# multikarya_mbed_rev_b_print.net
KiCad netlist of a schematic drawn in EAGLE
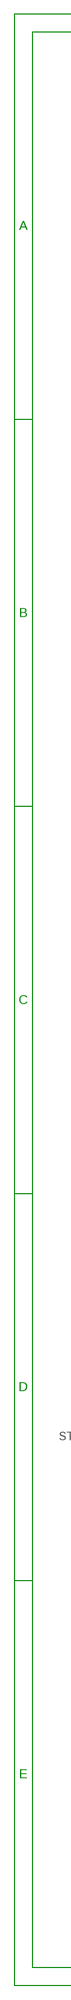
[diagram p0: schematic, sheet 1, part 1 of 2]
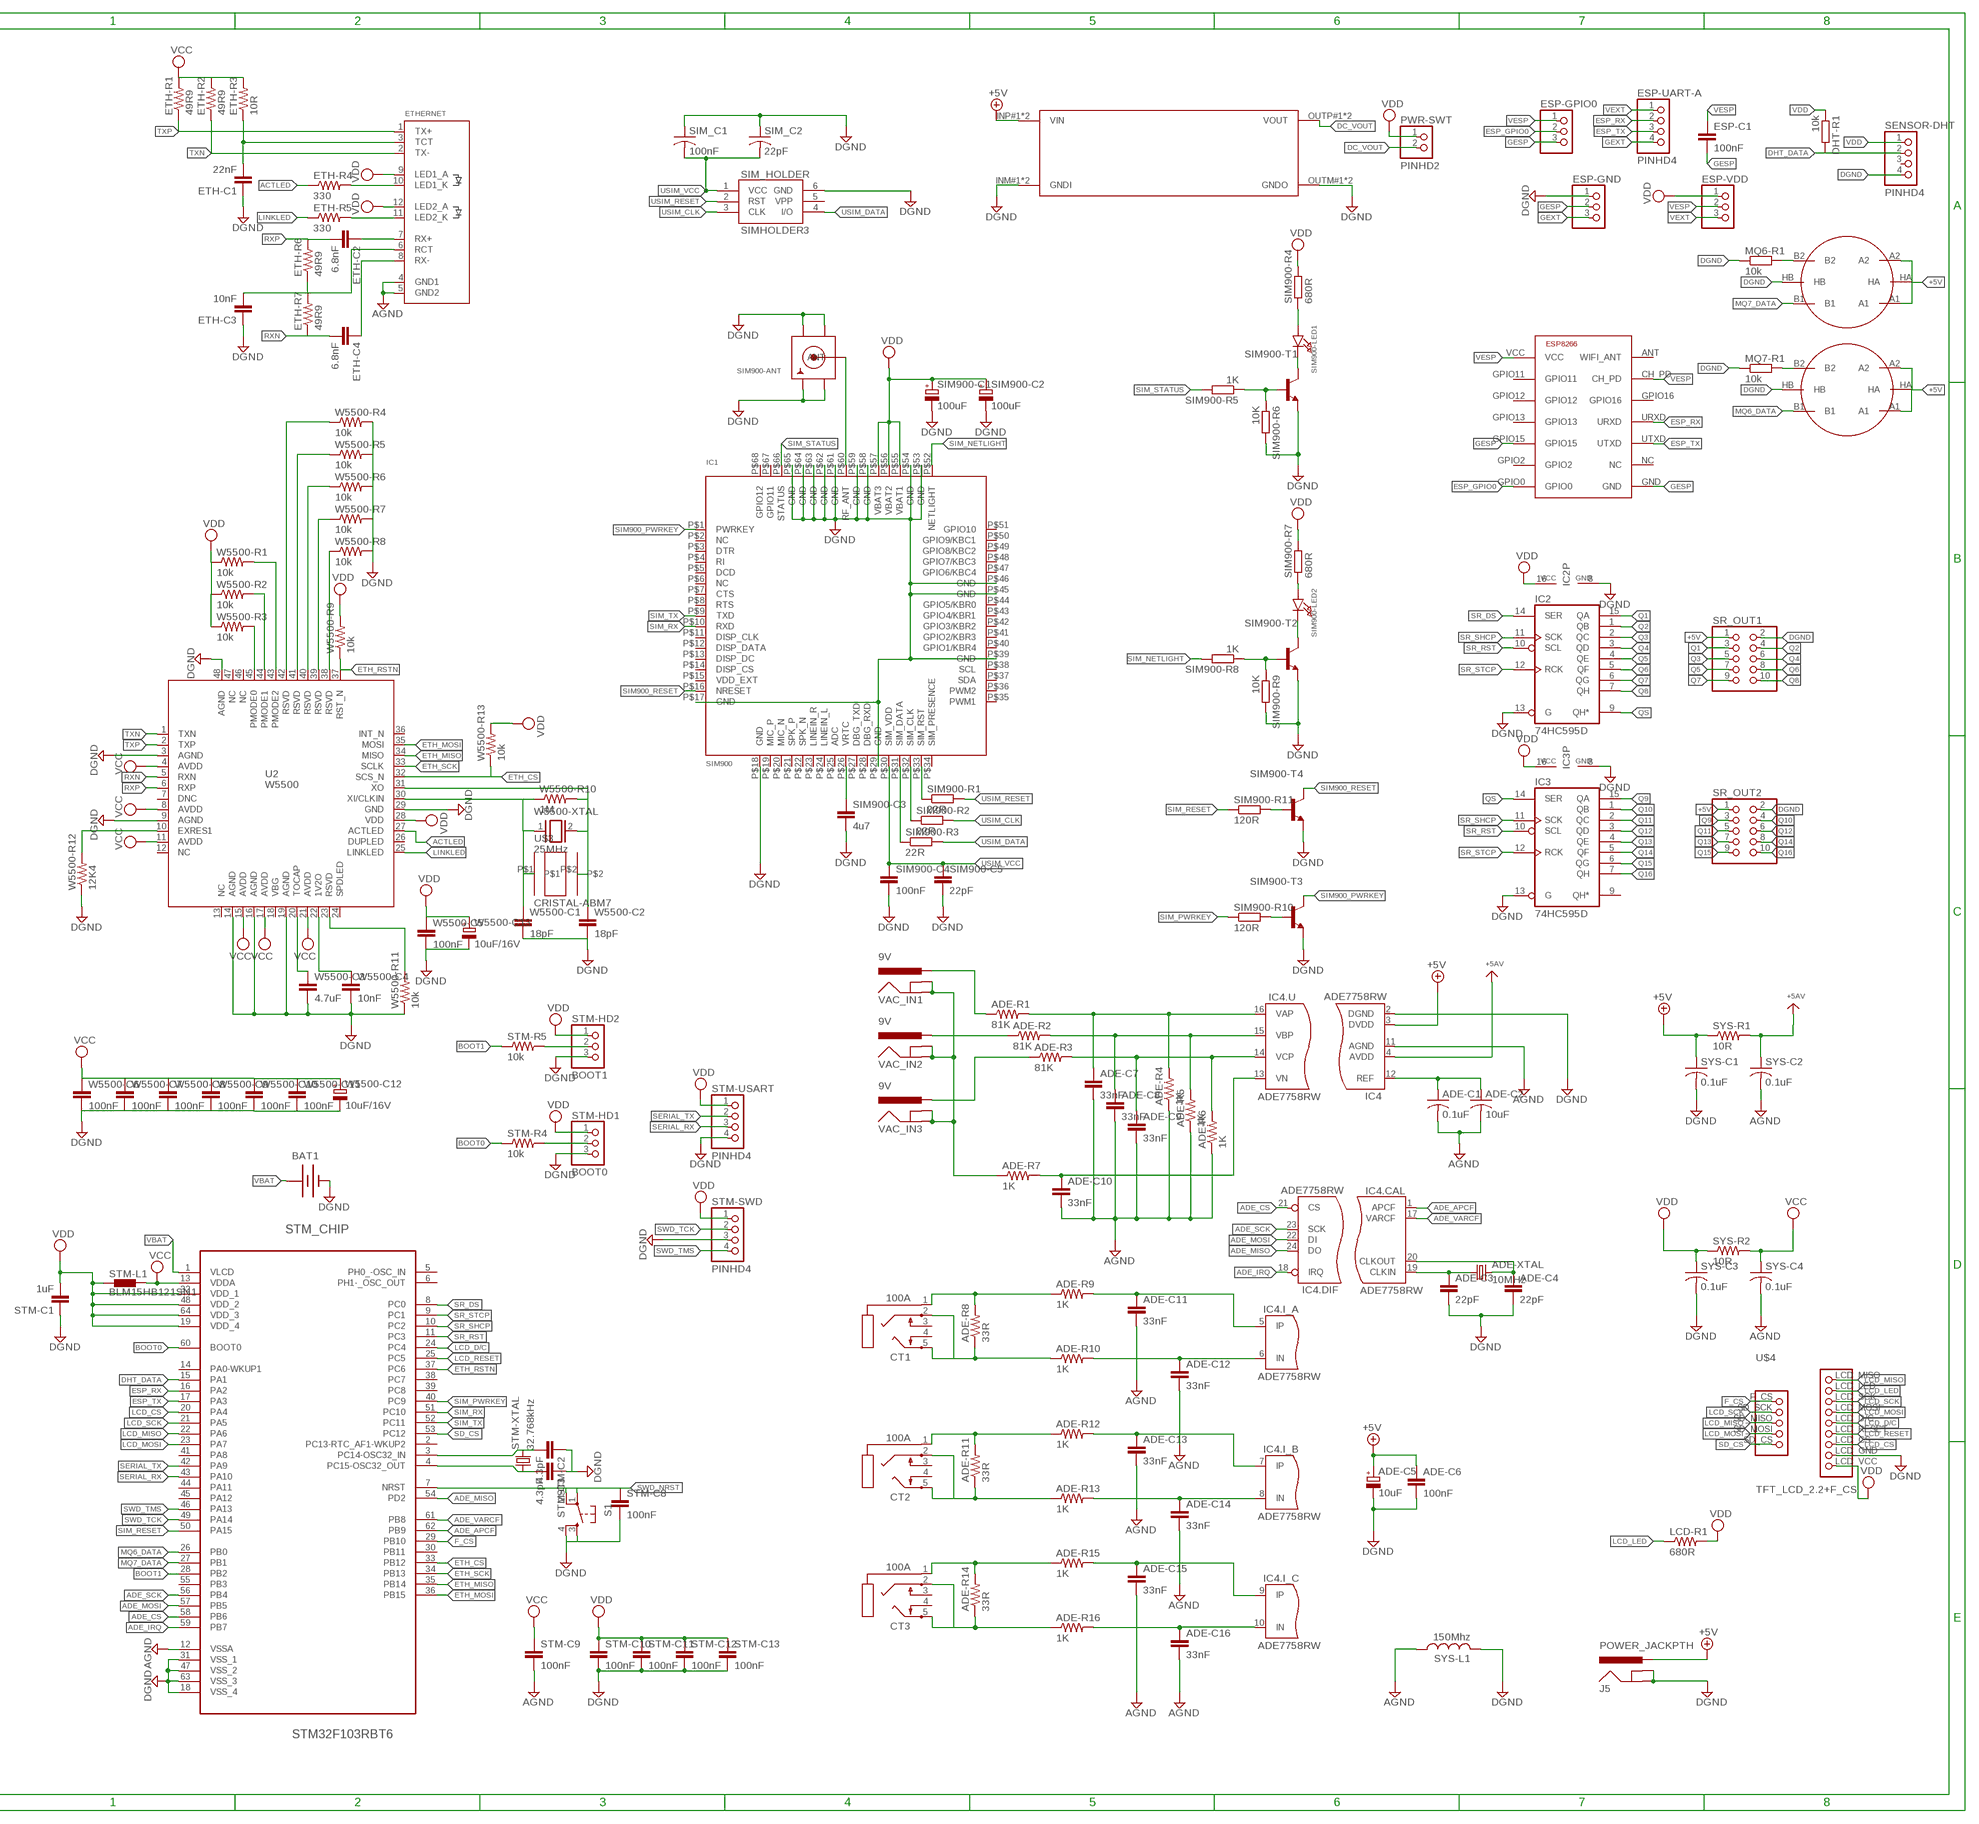
[diagram p1: schematic, sheet 1, part 2 of 2]

(export (version "E")
  (design (tool "Eeschema 10.0.6"))
  (components
    (comp (ref "ADE-C1")
      (value "0.1uF")
      (footprint "eagle-import:C0603@1")
      (libsource (lib "eagle-import") (part "C-USC0603"))
    )
    (comp (ref "ADE-C2")
      (value "10uF")
      (footprint "eagle-import:C0805K")
      (libsource (lib "eagle-import") (part "C-USC0805K"))
    )
    (comp (ref "ADE-C3")
      (value "22pF")
      (footprint "eagle-import:C0603")
      (libsource (lib "eagle-import") (part "C-EUC0603"))
    )
    (comp (ref "ADE-C4")
      (value "22pF")
      (footprint "eagle-import:C0603")
      (libsource (lib "eagle-import") (part "C-EUC0603"))
    )
    (comp (ref "ADE-C5")
      (value "10uF")
      (footprint "eagle-import:153CLV-0605")
      (libsource (lib "eagle-import") (part "CPOL-EU153CLV-0605"))
    )
    (comp (ref "ADE-C6")
      (value "100nF")
      (footprint "eagle-import:C0603")
      (libsource (lib "eagle-import") (part "C-EUC0603"))
    )
    (comp (ref "ADE-C7")
      (value "33nF")
      (footprint "eagle-import:0603-CAP")
      (libsource (lib "eagle-import") (part "CAP0603-CAP"))
    )
    (comp (ref "ADE-C8")
      (value "33nF")
      (footprint "eagle-import:0603-CAP")
      (libsource (lib "eagle-import") (part "CAP0603-CAP"))
    )
    (comp (ref "ADE-C9")
      (value "33nF")
      (footprint "eagle-import:0603-CAP")
      (libsource (lib "eagle-import") (part "CAP0603-CAP"))
    )
    (comp (ref "ADE-C10")
      (value "33nF")
      (footprint "eagle-import:0603-CAP")
      (libsource (lib "eagle-import") (part "CAP0603-CAP"))
    )
    (comp (ref "ADE-C11")
      (value "33nF")
      (footprint "eagle-import:0603-CAP")
      (libsource (lib "eagle-import") (part "CAP0603-CAP"))
    )
    (comp (ref "ADE-C12")
      (value "33nF")
      (footprint "eagle-import:0603-CAP")
      (libsource (lib "eagle-import") (part "CAP0603-CAP"))
    )
    (comp (ref "ADE-C13")
      (value "33nF")
      (footprint "eagle-import:0603-CAP")
      (libsource (lib "eagle-import") (part "CAP0603-CAP"))
    )
    (comp (ref "ADE-C14")
      (value "33nF")
      (footprint "eagle-import:0603-CAP")
      (libsource (lib "eagle-import") (part "CAP0603-CAP"))
    )
    (comp (ref "ADE-C15")
      (value "33nF")
      (footprint "eagle-import:0603-CAP")
      (libsource (lib "eagle-import") (part "CAP0603-CAP"))
    )
    (comp (ref "ADE-C16")
      (value "33nF")
      (footprint "eagle-import:0603-CAP")
      (libsource (lib "eagle-import") (part "CAP0603-CAP"))
    )
    (comp (ref "ADE-R1")
      (value "81K")
      (footprint "eagle-import:0603-RES")
      (libsource (lib "eagle-import") (part "RESISTOR0603-RES"))
    )
    (comp (ref "ADE-R2")
      (value "81K")
      (footprint "eagle-import:0603-RES")
      (libsource (lib "eagle-import") (part "RESISTOR0603-RES"))
    )
    (comp (ref "ADE-R3")
      (value "81K")
      (footprint "eagle-import:0603-RES")
      (libsource (lib "eagle-import") (part "RESISTOR0603-RES"))
    )
    (comp (ref "ADE-R4")
      (value "1K")
      (footprint "eagle-import:0603-RES")
      (libsource (lib "eagle-import") (part "RESISTOR0603-RES"))
    )
    (comp (ref "ADE-R5")
      (value "1K")
      (footprint "eagle-import:0603-RES")
      (libsource (lib "eagle-import") (part "RESISTOR0603-RES"))
    )
    (comp (ref "ADE-R6")
      (value "1K")
      (footprint "eagle-import:0603-RES")
      (libsource (lib "eagle-import") (part "RESISTOR0603-RES"))
    )
    (comp (ref "ADE-R7")
      (value "1K")
      (footprint "eagle-import:0603-RES")
      (libsource (lib "eagle-import") (part "RESISTOR0603-RES"))
    )
    (comp (ref "ADE-R8")
      (value "33R")
      (footprint "eagle-import:0603-RES")
      (libsource (lib "eagle-import") (part "RESISTOR0603-RES"))
    )
    (comp (ref "ADE-R9")
      (value "1K")
      (footprint "eagle-import:0603-RES")
      (libsource (lib "eagle-import") (part "RESISTOR0603-RES"))
    )
    (comp (ref "ADE-R10")
      (value "1K")
      (footprint "eagle-import:0603-RES")
      (libsource (lib "eagle-import") (part "RESISTOR0603-RES"))
    )
    (comp (ref "ADE-R11")
      (value "33R")
      (footprint "eagle-import:0603-RES")
      (libsource (lib "eagle-import") (part "RESISTOR0603-RES"))
    )
    (comp (ref "ADE-R12")
      (value "1K")
      (footprint "eagle-import:0603-RES")
      (libsource (lib "eagle-import") (part "RESISTOR0603-RES"))
    )
    (comp (ref "ADE-R13")
      (value "1K")
      (footprint "eagle-import:0603-RES")
      (libsource (lib "eagle-import") (part "RESISTOR0603-RES"))
    )
    (comp (ref "ADE-R14")
      (value "33R")
      (footprint "eagle-import:0603-RES")
      (libsource (lib "eagle-import") (part "RESISTOR0603-RES"))
    )
    (comp (ref "ADE-R15")
      (value "1K")
      (footprint "eagle-import:0603-RES")
      (libsource (lib "eagle-import") (part "RESISTOR0603-RES"))
    )
    (comp (ref "ADE-R16")
      (value "1K")
      (footprint "eagle-import:0603-RES")
      (libsource (lib "eagle-import") (part "RESISTOR0603-RES"))
    )
    (comp (ref "ADE-XTAL")
      (value "10MHz")
      (footprint "eagle-import:HC49US")
      (libsource (lib "eagle-import") (part "CRYSTALHC49US"))
    )
    (comp (ref "BAT1")
      (value "BATTERY20PTH")
      (footprint "eagle-import:BATTCOM_20MM_PTH")
      (libsource (lib "eagle-import") (part "BATTERY20PTH"))
    )
    (comp (ref "CT1")
      (value "100A")
      (footprint "eagle-import:STX3100")
      (libsource (lib "eagle-import") (part "AUDIO_STEREOJACK"))
    )
    (comp (ref "CT2")
      (value "100A")
      (footprint "eagle-import:STX3100")
      (libsource (lib "eagle-import") (part "AUDIO_STEREOJACK"))
    )
    (comp (ref "CT3")
      (value "100A")
      (footprint "eagle-import:STX3100")
      (libsource (lib "eagle-import") (part "AUDIO_STEREOJACK"))
    )
    (comp (ref "DCDC-3.5V")
      (value "DCDCMODULE_SMALL")
      (footprint "eagle-import:DCDCMODULE-SMALL")
      (libsource (lib "eagle-import") (part "DCDCMODULE_SMALL"))
    )
    (comp (ref "DHT-R1")
      (value "10k")
      (footprint "eagle-import:R0603")
      (libsource (lib "eagle-import") (part "resistor_R-EU_R0603"))
    )
    (comp (ref "ESP-C1")
      (value "100nF")
      (footprint "eagle-import:C0603")
      (libsource (lib "eagle-import") (part "C-EUC0603"))
    )
    (comp (ref "ESP-GND")
      (value "PINHD-1X3")
      (footprint "eagle-import:1X03")
      (libsource (lib "eagle-import") (part "PINHD-1X3"))
    )
    (comp (ref "ESP-GPIO0")
      (value "PINHD-1X3")
      (footprint "eagle-import:1X03")
      (libsource (lib "eagle-import") (part "PINHD-1X3"))
    )
    (comp (ref "ESP-UART-A")
      (value "PINHD4")
      (footprint "eagle-import:PINHD4")
      (libsource (lib "eagle-import") (part "PINHD4"))
    )
    (comp (ref "ESP-VDD")
      (value "PINHD-1X3")
      (footprint "eagle-import:1X03")
      (libsource (lib "eagle-import") (part "PINHD-1X3"))
    )
    (comp (ref "ESP8266")
      (value "ESP-07")
      (footprint "eagle-import:ESP-07")
      (libsource (lib "eagle-import") (part "ESP-07"))
    )
    (comp (ref "ETH-C1")
      (value "22nF")
      (footprint "eagle-import:C0603")
      (libsource (lib "eagle-import") (part "C-EUC0603"))
    )
    (comp (ref "ETH-C2")
      (value "6.8nF")
      (footprint "eagle-import:C0603")
      (libsource (lib "eagle-import") (part "C-EUC0603"))
    )
    (comp (ref "ETH-C3")
      (value "10nF")
      (footprint "eagle-import:C0603")
      (libsource (lib "eagle-import") (part "C-EUC0603"))
    )
    (comp (ref "ETH-C4")
      (value "6.8nF")
      (footprint "eagle-import:C0603")
      (libsource (lib "eagle-import") (part "C-EUC0603"))
    )
    (comp (ref "ETH-R1")
      (value "49R9")
      (footprint "eagle-import:R0603")
      (libsource (lib "eagle-import") (part "R-US_R0603"))
    )
    (comp (ref "ETH-R2")
      (value "49R9")
      (footprint "eagle-import:R0603")
      (libsource (lib "eagle-import") (part "R-US_R0603"))
    )
    (comp (ref "ETH-R3")
      (value "10R")
      (footprint "eagle-import:R0603")
      (libsource (lib "eagle-import") (part "R-US_R0603"))
    )
    (comp (ref "ETH-R4")
      (value "330")
      (footprint "eagle-import:R0603")
      (libsource (lib "eagle-import") (part "R-US_R0603"))
    )
    (comp (ref "ETH-R5")
      (value "330")
      (footprint "eagle-import:R0603")
      (libsource (lib "eagle-import") (part "R-US_R0603"))
    )
    (comp (ref "ETH-R6")
      (value "49R9")
      (footprint "eagle-import:R0603")
      (libsource (lib "eagle-import") (part "R-US_R0603"))
    )
    (comp (ref "ETH-R7")
      (value "49R9")
      (footprint "eagle-import:R0603")
      (libsource (lib "eagle-import") (part "R-US_R0603"))
    )
    (comp (ref "ETHERNET")
      (value "RJ45J0026D21BNL")
      (footprint "eagle-import:RJ45_PULSEJACK")
      (libsource (lib "eagle-import") (part "RJ45J0026D21BNL"))
    )
    (comp (ref "IC1")
      (value "SIM900")
      (footprint "eagle-import:SIM900_SMT")
      (libsource (lib "eagle-import") (part "GSM_SIM900_LITERAL"))
    )
    (comp (ref "IC2")
      (value "74HC595D")
      (footprint "eagle-import:SO16")
      (libsource (lib "eagle-import") (part "74595DHC"))
    )
    (comp (ref "IC3")
      (value "74HC595D")
      (footprint "eagle-import:SO16")
      (libsource (lib "eagle-import") (part "74595DHC"))
    )
    (comp (ref "IC4")
      (value "ADE7758RW")
      (footprint "eagle-import:SOIC24")
      (libsource (lib "eagle-import") (part "ADE7758RW"))
    )
    (comp (ref "J5")
      (value "POWER_JACKPTH")
      (footprint "eagle-import:POWER_JACK_PTH")
      (libsource (lib "eagle-import") (part "POWER_JACKPTH"))
    )
    (comp (ref "LCD-R1")
      (value "680R")
      (footprint "eagle-import:0603-RES")
      (libsource (lib "eagle-import") (part "RESISTOR0603-RES"))
    )
    (comp (ref "MQ6-R1")
      (value "10k")
      (footprint "eagle-import:R0603")
      (libsource (lib "eagle-import") (part "resistor_R-EU_R0603"))
    )
    (comp (ref "MQ7-R1")
      (value "10k")
      (footprint "eagle-import:R0603")
      (libsource (lib "eagle-import") (part "resistor_R-EU_R0603"))
    )
    (comp (ref "PWR-SWT")
      (value "PINHD2")
      (footprint "eagle-import:PINHD2")
      (libsource (lib "eagle-import") (part "PINHD2"))
    )
    (comp (ref "S1")
      (value "TAC_SWITCHPTH")
      (footprint "eagle-import:TACTILE-PTH")
      (libsource (lib "eagle-import") (part "TAC_SWITCHPTH"))
    )
    (comp (ref "SENSOR-DHT")
      (value "PINHD4")
      (footprint "eagle-import:PINHD4")
      (libsource (lib "eagle-import") (part "PINHD4"))
    )
    (comp (ref "SENSOR-MQ6")
      (value "METHANE_SENSOR")
      (footprint "eagle-import:MQ-3")
      (libsource (lib "eagle-import") (part "METHANE_SENSOR"))
    )
    (comp (ref "SENSOR-MQ7")
      (value "METHANE_SENSOR")
      (footprint "eagle-import:MQ-3")
      (libsource (lib "eagle-import") (part "METHANE_SENSOR"))
    )
    (comp (ref "SIM900-ANT")
      (value "SMACONNECTOR")
      (footprint "eagle-import:SMA90_DIP")
      (libsource (lib "eagle-import") (part "SMACONNECTOR"))
    )
    (comp (ref "SIM900-C1")
      (value "100uF")
      (footprint "eagle-import:153CLV-0605")
      (libsource (lib "eagle-import") (part "CPOL-EU153CLV-0605"))
    )
    (comp (ref "SIM900-C2")
      (value "100uF")
      (footprint "eagle-import:153CLV-0605")
      (libsource (lib "eagle-import") (part "CPOL-EU153CLV-0605"))
    )
    (comp (ref "SIM900-C3")
      (value "4u7")
      (footprint "eagle-import:C0603")
      (libsource (lib "eagle-import") (part "C-EUC0603"))
    )
    (comp (ref "SIM900-C4")
      (value "100nF")
      (footprint "eagle-import:C0603")
      (libsource (lib "eagle-import") (part "C-EUC0603"))
    )
    (comp (ref "SIM900-C5")
      (value "22pF")
      (footprint "eagle-import:C0603")
      (libsource (lib "eagle-import") (part "C-EUC0603"))
    )
    (comp (ref "SIM900-LED1")
      (value "LED0805_NOOUTLINE")
      (footprint "eagle-import:CHIPLED_0805_NOOUTLINE")
      (libsource (lib "eagle-import") (part "LED0805_NOOUTLINE"))
    )
    (comp (ref "SIM900-LED2")
      (value "LED0805_NOOUTLINE")
      (footprint "eagle-import:CHIPLED_0805_NOOUTLINE")
      (libsource (lib "eagle-import") (part "LED0805_NOOUTLINE"))
    )
    (comp (ref "SIM900-R1")
      (value "22R")
      (footprint "eagle-import:R0603")
      (libsource (lib "eagle-import") (part "R-EU_R0603"))
    )
    (comp (ref "SIM900-R2")
      (value "22R")
      (footprint "eagle-import:R0603")
      (libsource (lib "eagle-import") (part "R-EU_R0603"))
    )
    (comp (ref "SIM900-R3")
      (value "22R")
      (footprint "eagle-import:R0603")
      (libsource (lib "eagle-import") (part "R-EU_R0603"))
    )
    (comp (ref "SIM900-R4")
      (value "680R")
      (footprint "eagle-import:R0603")
      (libsource (lib "eagle-import") (part "R-EU_R0603"))
    )
    (comp (ref "SIM900-R5")
      (value "1K")
      (footprint "eagle-import:R0603")
      (libsource (lib "eagle-import") (part "R-EU_R0603"))
    )
    (comp (ref "SIM900-R6")
      (value "10K")
      (footprint "eagle-import:R0603")
      (libsource (lib "eagle-import") (part "R-EU_R0603"))
    )
    (comp (ref "SIM900-R7")
      (value "680R")
      (footprint "eagle-import:R0603")
      (libsource (lib "eagle-import") (part "R-EU_R0603"))
    )
    (comp (ref "SIM900-R8")
      (value "1K")
      (footprint "eagle-import:R0603")
      (libsource (lib "eagle-import") (part "R-EU_R0603"))
    )
    (comp (ref "SIM900-R9")
      (value "10K")
      (footprint "eagle-import:R0603")
      (libsource (lib "eagle-import") (part "R-EU_R0603"))
    )
    (comp (ref "SIM900-R10")
      (value "120R")
      (footprint "eagle-import:R0603")
      (libsource (lib "eagle-import") (part "resistor_R-EU_R0603"))
    )
    (comp (ref "SIM900-R11")
      (value "120R")
      (footprint "eagle-import:R0603")
      (libsource (lib "eagle-import") (part "resistor_R-EU_R0603"))
    )
    (comp (ref "SIM900-T1")
      (value "MMBT2222ALT1-NPN-SOT23-BEC")
      (footprint "eagle-import:SOT23-BEC")
      (libsource (lib "eagle-import") (part "-NPN-SOT23-BECMMBT2222ALT1"))
    )
    (comp (ref "SIM900-T2")
      (value "MMBT2222ALT1-NPN-SOT23-BEC")
      (footprint "eagle-import:SOT23-BEC")
      (libsource (lib "eagle-import") (part "-NPN-SOT23-BECMMBT2222ALT1"))
    )
    (comp (ref "SIM900-T3")
      (value "MMBT2222ALT1-NPN-SOT23-BEC")
      (footprint "eagle-import:SOT23-BEC")
      (libsource (lib "eagle-import") (part "transistor-neu-to92_-NPN-SOT23-BECMMBT2222ALT1"))
    )
    (comp (ref "SIM900-T4")
      (value "MMBT2222ALT1-NPN-SOT23-BEC")
      (footprint "eagle-import:SOT23-BEC")
      (libsource (lib "eagle-import") (part "transistor-neu-to92_-NPN-SOT23-BECMMBT2222ALT1"))
    )
    (comp (ref "SIM_C1")
      (value "100nF")
      (footprint "eagle-import:C0603K")
      (libsource (lib "eagle-import") (part "C-USC0603K"))
    )
    (comp (ref "SIM_C2")
      (value "22pF")
      (footprint "eagle-import:C0603K")
      (libsource (lib "eagle-import") (part "C-USC0603K"))
    )
    (comp (ref "SIM_HOLDER")
      (value "SIMHOLDER3")
      (footprint "eagle-import:SIMHOLDER3")
      (libsource (lib "eagle-import") (part "SIMHOLDER3"))
    )
    (comp (ref "SR_OUT1")
      (value "PINHD-2X5/90")
      (footprint "eagle-import:2X05_90")
      (libsource (lib "eagle-import") (part "PINHD-2X5/90"))
    )
    (comp (ref "SR_OUT2")
      (value "PINHD-2X5/90")
      (footprint "eagle-import:2X05_90")
      (libsource (lib "eagle-import") (part "PINHD-2X5/90"))
    )
    (comp (ref "STM-C1")
      (value "1uF")
      (footprint "eagle-import:C0603")
      (libsource (lib "eagle-import") (part "C-EUC0603"))
    )
    (comp (ref "STM-C2")
      (value "4.3pF")
      (footprint "eagle-import:C0603")
      (libsource (lib "eagle-import") (part "C-EUC0603"))
    )
    (comp (ref "STM-C3")
      (value "4.3pF")
      (footprint "eagle-import:C0603")
      (libsource (lib "eagle-import") (part "C-EUC0603"))
    )
    (comp (ref "STM-C8")
      (value "100nF")
      (footprint "eagle-import:C0603")
      (libsource (lib "eagle-import") (part "C-EUC0603"))
    )
    (comp (ref "STM-C9")
      (value "100nF")
      (footprint "eagle-import:C0603")
      (libsource (lib "eagle-import") (part "C-EUC0603"))
    )
    (comp (ref "STM-C10")
      (value "100nF")
      (footprint "eagle-import:C0603")
      (libsource (lib "eagle-import") (part "C-EUC0603"))
    )
    (comp (ref "STM-C11")
      (value "100nF")
      (footprint "eagle-import:C0603")
      (libsource (lib "eagle-import") (part "C-EUC0603"))
    )
    (comp (ref "STM-C12")
      (value "100nF")
      (footprint "eagle-import:C0603")
      (libsource (lib "eagle-import") (part "C-EUC0603"))
    )
    (comp (ref "STM-C13")
      (value "100nF")
      (footprint "eagle-import:C0603")
      (libsource (lib "eagle-import") (part "C-EUC0603"))
    )
    (comp (ref "STM-HD1")
      (value "BOOT0")
      (footprint "eagle-import:1X03")
      (libsource (lib "eagle-import") (part "PINHD-1X3"))
    )
    (comp (ref "STM-HD2")
      (value "BOOT1")
      (footprint "eagle-import:1X03")
      (libsource (lib "eagle-import") (part "PINHD-1X3"))
    )
    (comp (ref "STM-L1")
      (value "BLM15HB121SN1")
      (footprint "eagle-import:0402")
      (libsource (lib "eagle-import") (part "BLM15HB121SN1"))
    )
    (comp (ref "STM-R4")
      (value "10k")
      (footprint "eagle-import:R0603")
      (libsource (lib "eagle-import") (part "R-US_R0603"))
    )
    (comp (ref "STM-R5")
      (value "10k")
      (footprint "eagle-import:R0603")
      (libsource (lib "eagle-import") (part "R-US_R0603"))
    )
    (comp (ref "STM-SWD")
      (value "PINHD4")
      (footprint "eagle-import:PINHD4")
      (libsource (lib "eagle-import") (part "PINHD4"))
    )
    (comp (ref "STM-USART")
      (value "PINHD4")
      (footprint "eagle-import:PINHD4")
      (libsource (lib "eagle-import") (part "PINHD4"))
    )
    (comp (ref "STM-XTAL")
      (value "32.768kHz")
      (footprint "eagle-import:TC26H")
      (libsource (lib "eagle-import") (part "CRYSTALTC26H"))
    )
    (comp (ref "STM_CHIP")
      (value "STM32F103RBT6")
      (footprint "eagle-import:QFP50P1200X1200X160-64N")
      (fields (field (name "MPN") "STM32L152RBT6"))
      (libsource (lib "eagle-import") (part "STM32L152RBT6"))
    )
    (comp (ref "SYS-C1")
      (value "0.1uF")
      (footprint "eagle-import:C0603@1")
      (libsource (lib "eagle-import") (part "C-USC0603"))
    )
    (comp (ref "SYS-C2")
      (value "0.1uF")
      (footprint "eagle-import:C0603@1")
      (libsource (lib "eagle-import") (part "C-USC0603"))
    )
    (comp (ref "SYS-C3")
      (value "0.1uF")
      (footprint "eagle-import:C0603@1")
      (libsource (lib "eagle-import") (part "C-USC0603"))
    )
    (comp (ref "SYS-C4")
      (value "0.1uF")
      (footprint "eagle-import:C0603@1")
      (libsource (lib "eagle-import") (part "C-USC0603"))
    )
    (comp (ref "SYS-L1")
      (value "150Mhz")
      (footprint "eagle-import:POWER-CHOKE_WE-TPC")
      (libsource (lib "eagle-import") (part "L-USWE-TPC"))
    )
    (comp (ref "SYS-R1")
      (value "10R")
      (footprint "eagle-import:0603-RES")
      (libsource (lib "eagle-import") (part "RESISTOR0603-RES"))
    )
    (comp (ref "SYS-R2")
      (value "10R")
      (footprint "eagle-import:0603-RES")
      (libsource (lib "eagle-import") (part "RESISTOR0603-RES"))
    )
    (comp (ref "U$3")
      (value "CRISTAL-ABM7")
      (footprint "eagle-import:CRISTAL-ABM7")
      (libsource (lib "eagle-import") (part "CRISTAL-ABM7"))
    )
    (comp (ref "U$4")
      (value "TFT_LCD_2.2+F_CS")
      (footprint "eagle-import:TFT_LCD_2.2+F_CS")
      (libsource (lib "eagle-import") (part "TFT_LCD_2.2+F_CS"))
    )
    (comp (ref "U2")
      (value "W5500")
      (footprint "eagle-import:W5500")
      (libsource (lib "eagle-import") (part "W5500"))
    )
    (comp (ref "VAC_IN1")
      (value "9V")
      (footprint "eagle-import:POWER_JACK_PTH")
      (libsource (lib "eagle-import") (part "POWER_JACKPTH"))
    )
    (comp (ref "VAC_IN2")
      (value "9V")
      (footprint "eagle-import:POWER_JACK_PTH")
      (libsource (lib "eagle-import") (part "POWER_JACKPTH"))
    )
    (comp (ref "VAC_IN3")
      (value "9V")
      (footprint "eagle-import:POWER_JACK_PTH")
      (libsource (lib "eagle-import") (part "POWER_JACKPTH"))
    )
    (comp (ref "W5500-C1")
      (value "18pF")
      (footprint "eagle-import:C0603")
      (libsource (lib "eagle-import") (part "C-EUC0603"))
    )
    (comp (ref "W5500-C2")
      (value "18pF")
      (footprint "eagle-import:C0603")
      (libsource (lib "eagle-import") (part "C-EUC0603"))
    )
    (comp (ref "W5500-C3")
      (value "4.7uF")
      (footprint "eagle-import:C0603")
      (libsource (lib "eagle-import") (part "C-EUC0603"))
    )
    (comp (ref "W5500-C4")
      (value "10nF")
      (footprint "eagle-import:C0603")
      (libsource (lib "eagle-import") (part "C-EUC0603"))
    )
    (comp (ref "W5500-C5")
      (value "100nF")
      (footprint "eagle-import:C0603")
      (libsource (lib "eagle-import") (part "C-EUC0603"))
    )
    (comp (ref "W5500-C6")
      (value "100nF")
      (footprint "eagle-import:C0603")
      (libsource (lib "eagle-import") (part "C-EUC0603"))
    )
    (comp (ref "W5500-C7")
      (value "100nF")
      (footprint "eagle-import:C0603")
      (libsource (lib "eagle-import") (part "C-EUC0603"))
    )
    (comp (ref "W5500-C8")
      (value "100nF")
      (footprint "eagle-import:C0603")
      (libsource (lib "eagle-import") (part "C-EUC0603"))
    )
    (comp (ref "W5500-C9")
      (value "100nF")
      (footprint "eagle-import:C0603")
      (libsource (lib "eagle-import") (part "C-EUC0603"))
    )
    (comp (ref "W5500-C10")
      (value "100nF")
      (footprint "eagle-import:C0603")
      (libsource (lib "eagle-import") (part "C-EUC0603"))
    )
    (comp (ref "W5500-C11")
      (value "100nF")
      (footprint "eagle-import:C0603")
      (libsource (lib "eagle-import") (part "C-EUC0603"))
    )
    (comp (ref "W5500-C12")
      (value "10uF/16V")
      (footprint "eagle-import:153CLV-0605")
      (libsource (lib "eagle-import") (part "CPOL-EU153CLV-0605"))
    )
    (comp (ref "W5500-C13")
      (value "10uF/16V")
      (footprint "eagle-import:153CLV-0605")
      (libsource (lib "eagle-import") (part "CPOL-EU153CLV-0605"))
    )
    (comp (ref "W5500-R1")
      (value "10k")
      (footprint "eagle-import:R0603")
      (libsource (lib "eagle-import") (part "R-US_R0603"))
    )
    (comp (ref "W5500-R2")
      (value "10k")
      (footprint "eagle-import:R0603")
      (libsource (lib "eagle-import") (part "R-US_R0603"))
    )
    (comp (ref "W5500-R3")
      (value "10k")
      (footprint "eagle-import:R0603")
      (libsource (lib "eagle-import") (part "R-US_R0603"))
    )
    (comp (ref "W5500-R4")
      (value "10k")
      (footprint "eagle-import:R0603")
      (libsource (lib "eagle-import") (part "R-US_R0603"))
    )
    (comp (ref "W5500-R5")
      (value "10k")
      (footprint "eagle-import:R0603")
      (libsource (lib "eagle-import") (part "R-US_R0603"))
    )
    (comp (ref "W5500-R6")
      (value "10k")
      (footprint "eagle-import:R0603")
      (libsource (lib "eagle-import") (part "R-US_R0603"))
    )
    (comp (ref "W5500-R7")
      (value "10k")
      (footprint "eagle-import:R0603")
      (libsource (lib "eagle-import") (part "R-US_R0603"))
    )
    (comp (ref "W5500-R8")
      (value "10k")
      (footprint "eagle-import:R0603")
      (libsource (lib "eagle-import") (part "R-US_R0603"))
    )
    (comp (ref "W5500-R9")
      (value "10k")
      (footprint "eagle-import:R0603")
      (libsource (lib "eagle-import") (part "R-US_R0603"))
    )
    (comp (ref "W5500-R10")
      (value "1M")
      (footprint "eagle-import:R0603")
      (libsource (lib "eagle-import") (part "R-US_R0603"))
    )
    (comp (ref "W5500-R11")
      (value "10k")
      (footprint "eagle-import:R0603")
      (libsource (lib "eagle-import") (part "R-US_R0603"))
    )
    (comp (ref "W5500-R12")
      (value "12K4")
      (footprint "eagle-import:R0805")
      (libsource (lib "eagle-import") (part "R-US_R0805"))
    )
    (comp (ref "W5500-R13")
      (value "10k")
      (footprint "eagle-import:R0603")
      (libsource (lib "eagle-import") (part "R-US_R0603"))
    )
    (comp (ref "W5500-XTAL")
      (value "25MHz")
      (footprint "eagle-import:QS")
      (libsource (lib "eagle-import") (part "XTAL/S"))
    )
  )
  (nets
    (net (code "1") (name "+5AV") (class "Default")
      (node (ref "IC4") (pin "4") (pinfunction "AVDD_4") (pintype "power_in"))
      (node (ref "SYS-C2") (pin "1") (pinfunction "1_1") (pintype "passive"))
      (node (ref "SYS-R1") (pin "2") (pinfunction "2_2") (pintype "passive"))
    )
    (net (code "2") (name "+5V") (class "Default")
      (node (ref "ADE-C5") (pin "+") (pinfunction "+_+") (pintype "passive"))
      (node (ref "ADE-C6") (pin "1") (pinfunction "1_1") (pintype "passive"))
      (node (ref "DCDC-3.5V") (pin "INP#1") (pinfunction "VIN_INP#1") (pintype "bidirectional"))
      (node (ref "DCDC-3.5V") (pin "INP#2") (pinfunction "VIN_INP#2") (pintype "bidirectional"))
      (node (ref "IC4") (pin "3") (pinfunction "DVDD_3") (pintype "power_in"))
      (node (ref "J5") (pin "PWR") (pinfunction "PWR_PWR") (pintype "bidirectional"))
      (node (ref "SENSOR-MQ6") (pin "A1") (pinfunction "A1_A1") (pintype "bidirectional"))
      (node (ref "SENSOR-MQ6") (pin "A2") (pinfunction "A2_A2") (pintype "bidirectional"))
      (node (ref "SENSOR-MQ6") (pin "HA") (pinfunction "HA_HA") (pintype "bidirectional"))
      (node (ref "SENSOR-MQ7") (pin "A1") (pinfunction "A1_A1") (pintype "bidirectional"))
      (node (ref "SENSOR-MQ7") (pin "A2") (pinfunction "A2_A2") (pintype "bidirectional"))
      (node (ref "SENSOR-MQ7") (pin "HA") (pinfunction "HA_HA") (pintype "bidirectional"))
      (node (ref "SR_OUT1") (pin "1") (pinfunction "1_1") (pintype "passive"))
      (node (ref "SR_OUT2") (pin "1") (pinfunction "1_1") (pintype "passive"))
      (node (ref "SYS-C1") (pin "1") (pinfunction "1_1") (pintype "passive"))
      (node (ref "SYS-R1") (pin "1") (pinfunction "1_1") (pintype "passive"))
    )
    (net (code "3") (name "/GPIO11") (class "Default")
      (node (ref "IC1") (pin "P$67") (pinfunction "GPIO11_P$67") (pintype "power_in"))
    )
    (net (code "4") (name "/GPIO12") (class "Default")
      (node (ref "IC1") (pin "P$68") (pinfunction "GPIO12_P$68") (pintype "power_in"))
    )
    (net (code "5") (name "ACTLED") (class "Default")
      (node (ref "ETH-R4") (pin "1") (pinfunction "1_1") (pintype "passive"))
      (node (ref "U2") (pin "27") (pinfunction "ACTLED_27") (pintype "passive"))
    )
    (net (code "6") (name "ADE_APCF") (class "Default")
      (node (ref "IC4") (pin "1") (pinfunction "APCF_1") (pintype "output"))
      (node (ref "STM_CHIP") (pin "62") (pinfunction "PB9_62") (pintype "bidirectional"))
    )
    (net (code "7") (name "ADE_CS") (class "Default")
      (node (ref "IC4") (pin "21") (pinfunction "CS_21") (pintype "input"))
      (node (ref "STM_CHIP") (pin "58") (pinfunction "PB6_58") (pintype "bidirectional"))
    )
    (net (code "8") (name "ADE_IRQ") (class "Default")
      (node (ref "IC4") (pin "18") (pinfunction "IRQ_18") (pintype "output"))
      (node (ref "STM_CHIP") (pin "59") (pinfunction "PB7_59") (pintype "bidirectional"))
    )
    (net (code "9") (name "ADE_MISO") (class "Default")
      (node (ref "IC4") (pin "24") (pinfunction "DO_24") (pintype "output"))
      (node (ref "STM_CHIP") (pin "54") (pinfunction "PD2_54") (pintype "bidirectional"))
    )
    (net (code "10") (name "ADE_MOSI") (class "Default")
      (node (ref "IC4") (pin "22") (pinfunction "DI_22") (pintype "input"))
      (node (ref "STM_CHIP") (pin "57") (pinfunction "PB5_57") (pintype "bidirectional"))
    )
    (net (code "11") (name "ADE_SCK") (class "Default")
      (node (ref "IC4") (pin "23") (pinfunction "SCK_23") (pintype "input"))
      (node (ref "STM_CHIP") (pin "56") (pinfunction "PB4_56") (pintype "bidirectional"))
    )
    (net (code "12") (name "ADE_VARCF") (class "Default")
      (node (ref "IC4") (pin "17") (pinfunction "VARCF_17") (pintype "output"))
      (node (ref "STM_CHIP") (pin "61") (pinfunction "PB8_61") (pintype "bidirectional"))
    )
    (net (code "13") (name "AGND") (class "Default")
      (node (ref "ADE-C1") (pin "2") (pinfunction "2_2") (pintype "passive"))
      (node (ref "ADE-C10") (pin "2") (pinfunction "2_2") (pintype "passive"))
      (node (ref "ADE-C11") (pin "2") (pinfunction "2_2") (pintype "passive"))
      (node (ref "ADE-C12") (pin "2") (pinfunction "2_2") (pintype "passive"))
      (node (ref "ADE-C13") (pin "2") (pinfunction "2_2") (pintype "passive"))
      (node (ref "ADE-C14") (pin "2") (pinfunction "2_2") (pintype "passive"))
      (node (ref "ADE-C15") (pin "2") (pinfunction "2_2") (pintype "passive"))
      (node (ref "ADE-C16") (pin "2") (pinfunction "2_2") (pintype "passive"))
      (node (ref "ADE-C2") (pin "2") (pinfunction "2_2") (pintype "passive"))
      (node (ref "ADE-C7") (pin "2") (pinfunction "2_2") (pintype "passive"))
      (node (ref "ADE-C8") (pin "2") (pinfunction "2_2") (pintype "passive"))
      (node (ref "ADE-C9") (pin "2") (pinfunction "2_2") (pintype "passive"))
      (node (ref "ADE-R4") (pin "1") (pinfunction "1_1") (pintype "passive"))
      (node (ref "ADE-R5") (pin "1") (pinfunction "1_1") (pintype "passive"))
      (node (ref "ADE-R6") (pin "1") (pinfunction "1_1") (pintype "passive"))
      (node (ref "ETHERNET") (pin "4") (pinfunction "GND1_4") (pintype "bidirectional"))
      (node (ref "ETHERNET") (pin "5") (pinfunction "GND2_5") (pintype "bidirectional"))
      (node (ref "IC4") (pin "11") (pinfunction "AGND_11") (pintype "power_in"))
      (node (ref "STM-C9") (pin "2") (pinfunction "2_2") (pintype "passive"))
      (node (ref "STM_CHIP") (pin "12") (pinfunction "VSSA_12") (pintype "power_in"))
      (node (ref "SYS-C2") (pin "2") (pinfunction "2_2") (pintype "passive"))
      (node (ref "SYS-C4") (pin "2") (pinfunction "2_2") (pintype "passive"))
      (node (ref "SYS-L1") (pin "1") (pinfunction "1_1") (pintype "passive"))
    )
    (net (code "14") (name "BOOT0") (class "Default")
      (node (ref "STM-R4") (pin "1") (pinfunction "1_1") (pintype "passive"))
      (node (ref "STM_CHIP") (pin "60") (pinfunction "BOOT0_60") (pintype "input"))
    )
    (net (code "15") (name "BOOT1") (class "Default")
      (node (ref "STM-R5") (pin "1") (pinfunction "1_1") (pintype "passive"))
      (node (ref "STM_CHIP") (pin "28") (pinfunction "PB2_28") (pintype "bidirectional"))
    )
    (net (code "16") (name "DC_VOUT") (class "Default")
      (node (ref "DCDC-3.5V") (pin "OUTP#1") (pinfunction "VOUT_OUTP#1") (pintype "bidirectional"))
      (node (ref "DCDC-3.5V") (pin "OUTP#2") (pinfunction "VOUT_OUTP#2") (pintype "bidirectional"))
      (node (ref "PWR-SWT") (pin "2") (pinfunction "2_2") (pintype "passive"))
    )
    (net (code "17") (name "DGND") (class "Default")
      (node (ref "ADE-C3") (pin "2") (pinfunction "2_2") (pintype "passive"))
      (node (ref "ADE-C4") (pin "2") (pinfunction "2_2") (pintype "passive"))
      (node (ref "ADE-C5") (pin "-") (pinfunction "-_-") (pintype "passive"))
      (node (ref "ADE-C6") (pin "2") (pinfunction "2_2") (pintype "passive"))
      (node (ref "BAT1") (pin "2") (pinfunction "-_2") (pintype "power_in"))
      (node (ref "DCDC-3.5V") (pin "INM#1") (pinfunction "GNDI_INM#1") (pintype "bidirectional"))
      (node (ref "DCDC-3.5V") (pin "INM#2") (pinfunction "GNDI_INM#2") (pintype "bidirectional"))
      (node (ref "DCDC-3.5V") (pin "OUTM#1") (pinfunction "GNDO_OUTM#1") (pintype "bidirectional"))
      (node (ref "DCDC-3.5V") (pin "OUTM#2") (pinfunction "GNDO_OUTM#2") (pintype "bidirectional"))
      (node (ref "ESP-GND") (pin "1") (pinfunction "1_1") (pintype "passive"))
      (node (ref "ETH-C1") (pin "1") (pinfunction "1_1") (pintype "passive"))
      (node (ref "ETH-C3") (pin "1") (pinfunction "1_1") (pintype "passive"))
      (node (ref "IC1") (pin "P$17") (pinfunction "GND_P$17") (pintype "power_in"))
      (node (ref "IC1") (pin "P$18") (pinfunction "GND_P$18") (pintype "power_in"))
      (node (ref "IC1") (pin "P$29") (pinfunction "GND_P$29") (pintype "power_in"))
      (node (ref "IC1") (pin "P$39") (pinfunction "GND_P$39") (pintype "power_in"))
      (node (ref "IC1") (pin "P$45") (pinfunction "GND_P$45") (pintype "power_in"))
      (node (ref "IC1") (pin "P$46") (pinfunction "GND_P$46") (pintype "power_in"))
      (node (ref "IC1") (pin "P$53") (pinfunction "GND_P$53") (pintype "power_in"))
      (node (ref "IC1") (pin "P$54") (pinfunction "GND_P$54") (pintype "power_in"))
      (node (ref "IC1") (pin "P$58") (pinfunction "GND_P$58") (pintype "power_in"))
      (node (ref "IC1") (pin "P$59") (pinfunction "GND_P$59") (pintype "power_in"))
      (node (ref "IC1") (pin "P$61") (pinfunction "GND_P$61") (pintype "power_in"))
      (node (ref "IC1") (pin "P$62") (pinfunction "GND_P$62") (pintype "power_in"))
      (node (ref "IC1") (pin "P$63") (pinfunction "GND_P$63") (pintype "power_in"))
      (node (ref "IC1") (pin "P$64") (pinfunction "GND_P$64") (pintype "power_in"))
      (node (ref "IC1") (pin "P$65") (pinfunction "GND_P$65") (pintype "power_in"))
      (node (ref "IC2") (pin "13") (pinfunction "G_13") (pintype "input"))
      (node (ref "IC2") (pin "8") (pinfunction "GND_8") (pintype "power_in"))
      (node (ref "IC3") (pin "13") (pinfunction "G_13") (pintype "input"))
      (node (ref "IC3") (pin "8") (pinfunction "GND_8") (pintype "power_in"))
      (node (ref "IC4") (pin "2") (pinfunction "DGND_2") (pintype "power_in"))
      (node (ref "J5") (pin "GND") (pinfunction "GND_GND") (pintype "bidirectional"))
      (node (ref "J5") (pin "GNDBREAK") (pinfunction "GNDBREAK_GNDBREAK") (pintype "bidirectional"))
      (node (ref "MQ6-R1") (pin "1") (pinfunction "1_1") (pintype "passive"))
      (node (ref "MQ7-R1") (pin "1") (pinfunction "1_1") (pintype "passive"))
      (node (ref "S1") (pin "3") (pinfunction "3_3") (pintype "passive"))
      (node (ref "S1") (pin "4") (pinfunction "4_4") (pintype "passive"))
      (node (ref "SENSOR-DHT") (pin "4") (pinfunction "4_4") (pintype "passive"))
      (node (ref "SENSOR-MQ6") (pin "HB") (pinfunction "HB_HB") (pintype "bidirectional"))
      (node (ref "SENSOR-MQ7") (pin "HB") (pinfunction "HB_HB") (pintype "bidirectional"))
      (node (ref "SIM900-ANT") (pin "GND1") (pinfunction "GND1_GND1") (pintype "power_in"))
      (node (ref "SIM900-ANT") (pin "GND2") (pinfunction "GND2_GND2") (pintype "power_in"))
      (node (ref "SIM900-ANT") (pin "GND3") (pinfunction "GND3_GND3") (pintype "power_in"))
      (node (ref "SIM900-ANT") (pin "GND4") (pinfunction "GND4_GND4") (pintype "power_in"))
      (node (ref "SIM900-C1") (pin "-") (pinfunction "-_-") (pintype "passive"))
      (node (ref "SIM900-C2") (pin "-") (pinfunction "-_-") (pintype "passive"))
      (node (ref "SIM900-C3") (pin "2") (pinfunction "2_2") (pintype "passive"))
      (node (ref "SIM900-C4") (pin "2") (pinfunction "2_2") (pintype "passive"))
      (node (ref "SIM900-C5") (pin "2") (pinfunction "2_2") (pintype "passive"))
      (node (ref "SIM900-R6") (pin "2") (pinfunction "2_2") (pintype "passive"))
      (node (ref "SIM900-R9") (pin "2") (pinfunction "2_2") (pintype "passive"))
      (node (ref "SIM900-T1") (pin "E") (pinfunction "E_E") (pintype "passive"))
      (node (ref "SIM900-T2") (pin "E") (pinfunction "E_E") (pintype "passive"))
      (node (ref "SIM900-T3") (pin "E") (pinfunction "E_E") (pintype "passive"))
      (node (ref "SIM900-T4") (pin "E") (pinfunction "E_E") (pintype "passive"))
      (node (ref "SIM_C1") (pin "1") (pinfunction "1_1") (pintype "passive"))
      (node (ref "SIM_C2") (pin "1") (pinfunction "1_1") (pintype "passive"))
      (node (ref "SIM_HOLDER") (pin "6") (pinfunction "GND_6") (pintype "bidirectional"))
      (node (ref "SR_OUT1") (pin "2") (pinfunction "2_2") (pintype "passive"))
      (node (ref "SR_OUT2") (pin "2") (pinfunction "2_2") (pintype "passive"))
      (node (ref "STM-C1") (pin "1") (pinfunction "1_1") (pintype "passive"))
      (node (ref "STM-C10") (pin "2") (pinfunction "2_2") (pintype "passive"))
      (node (ref "STM-C11") (pin "2") (pinfunction "2_2") (pintype "passive"))
      (node (ref "STM-C12") (pin "2") (pinfunction "2_2") (pintype "passive"))
      (node (ref "STM-C13") (pin "2") (pinfunction "2_2") (pintype "passive"))
      (node (ref "STM-C2") (pin "1") (pinfunction "1_1") (pintype "passive"))
      (node (ref "STM-C3") (pin "1") (pinfunction "1_1") (pintype "passive"))
      (node (ref "STM-C8") (pin "2") (pinfunction "2_2") (pintype "passive"))
      (node (ref "STM-HD1") (pin "3") (pinfunction "3_3") (pintype "passive"))
      (node (ref "STM-HD2") (pin "3") (pinfunction "3_3") (pintype "passive"))
      (node (ref "STM-SWD") (pin "3") (pinfunction "3_3") (pintype "passive"))
      (node (ref "STM-USART") (pin "4") (pinfunction "4_4") (pintype "passive"))
      (node (ref "STM_CHIP") (pin "18") (pinfunction "VSS_4_18") (pintype "power_in"))
      (node (ref "STM_CHIP") (pin "31") (pinfunction "VSS_1_31") (pintype "power_in"))
      (node (ref "STM_CHIP") (pin "47") (pinfunction "VSS_2_47") (pintype "power_in"))
      (node (ref "STM_CHIP") (pin "63") (pinfunction "VSS_3_63") (pintype "power_in"))
      (node (ref "SYS-C1") (pin "2") (pinfunction "2_2") (pintype "passive"))
      (node (ref "SYS-C3") (pin "2") (pinfunction "2_2") (pintype "passive"))
      (node (ref "SYS-L1") (pin "2") (pinfunction "2_2") (pintype "passive"))
      (node (ref "U$4") (pin "LCD_GND") (pinfunction "LCD_GND_LCD_GND") (pintype "passive"))
      (node (ref "U2") (pin "14") (pinfunction "AGND_14") (pintype "passive"))
      (node (ref "U2") (pin "16") (pinfunction "AGND_16") (pintype "passive"))
      (node (ref "U2") (pin "19") (pinfunction "AGND_19") (pintype "passive"))
      (node (ref "U2") (pin "29") (pinfunction "GND_29") (pintype "passive"))
      (node (ref "U2") (pin "3") (pinfunction "AGND_3") (pintype "passive"))
      (node (ref "U2") (pin "48") (pinfunction "AGND_48") (pintype "passive"))
      (node (ref "U2") (pin "9") (pinfunction "AGND_9") (pintype "passive"))
      (node (ref "W5500-C1") (pin "2") (pinfunction "2_2") (pintype "passive"))
      (node (ref "W5500-C10") (pin "2") (pinfunction "2_2") (pintype "passive"))
      (node (ref "W5500-C11") (pin "2") (pinfunction "2_2") (pintype "passive"))
      (node (ref "W5500-C12") (pin "-") (pinfunction "-_-") (pintype "passive"))
      (node (ref "W5500-C13") (pin "-") (pinfunction "-_-") (pintype "passive"))
      (node (ref "W5500-C2") (pin "2") (pinfunction "2_2") (pintype "passive"))
      (node (ref "W5500-C3") (pin "2") (pinfunction "2_2") (pintype "passive"))
      (node (ref "W5500-C4") (pin "2") (pinfunction "2_2") (pintype "passive"))
      (node (ref "W5500-C5") (pin "2") (pinfunction "2_2") (pintype "passive"))
      (node (ref "W5500-C6") (pin "2") (pinfunction "2_2") (pintype "passive"))
      (node (ref "W5500-C7") (pin "2") (pinfunction "2_2") (pintype "passive"))
      (node (ref "W5500-C8") (pin "2") (pinfunction "2_2") (pintype "passive"))
      (node (ref "W5500-C9") (pin "2") (pinfunction "2_2") (pintype "passive"))
      (node (ref "W5500-R11") (pin "1") (pinfunction "1_1") (pintype "passive"))
      (node (ref "W5500-R12") (pin "1") (pinfunction "1_1") (pintype "passive"))
      (node (ref "W5500-R4") (pin "2") (pinfunction "2_2") (pintype "passive"))
      (node (ref "W5500-R5") (pin "2") (pinfunction "2_2") (pintype "passive"))
      (node (ref "W5500-R6") (pin "2") (pinfunction "2_2") (pintype "passive"))
      (node (ref "W5500-R7") (pin "2") (pinfunction "2_2") (pintype "passive"))
      (node (ref "W5500-R8") (pin "2") (pinfunction "2_2") (pintype "passive"))
    )
    (net (code "18") (name "DHT_DATA") (class "Default")
      (node (ref "DHT-R1") (pin "2") (pinfunction "2_2") (pintype "passive"))
      (node (ref "SENSOR-DHT") (pin "2") (pinfunction "2_2") (pintype "passive"))
      (node (ref "STM_CHIP") (pin "15") (pinfunction "PA1_15") (pintype "bidirectional"))
    )
    (net (code "19") (name "ESP_GPIO0") (class "Default")
      (node (ref "ESP-GPIO0") (pin "2") (pinfunction "2_2") (pintype "passive"))
      (node (ref "ESP8266") (pin "GPIO0") (pinfunction "GPIO0_GPIO0") (pintype "bidirectional"))
    )
    (net (code "20") (name "ESP_RX") (class "Default")
      (node (ref "ESP-UART-A") (pin "2") (pinfunction "2_2") (pintype "passive"))
      (node (ref "ESP8266") (pin "URXD") (pinfunction "URXD_URXD") (pintype "bidirectional"))
      (node (ref "STM_CHIP") (pin "16") (pinfunction "PA2_16") (pintype "bidirectional"))
    )
    (net (code "21") (name "ESP_TX") (class "Default")
      (node (ref "ESP-UART-A") (pin "3") (pinfunction "3_3") (pintype "passive"))
      (node (ref "ESP8266") (pin "UTXD") (pinfunction "UTXD_UTXD") (pintype "bidirectional"))
      (node (ref "STM_CHIP") (pin "17") (pinfunction "PA3_17") (pintype "bidirectional"))
    )
    (net (code "22") (name "ETH_CS") (class "Default")
      (node (ref "STM_CHIP") (pin "33") (pinfunction "PB12_33") (pintype "bidirectional"))
      (node (ref "U2") (pin "32") (pinfunction "SCS_N_32") (pintype "passive"))
      (node (ref "W5500-R13") (pin "1") (pinfunction "1_1") (pintype "passive"))
    )
    (net (code "23") (name "ETH_MISO") (class "Default")
      (node (ref "STM_CHIP") (pin "35") (pinfunction "PB14_35") (pintype "bidirectional"))
      (node (ref "U2") (pin "34") (pinfunction "MISO_34") (pintype "passive"))
    )
    (net (code "24") (name "ETH_MOSI") (class "Default")
      (node (ref "STM_CHIP") (pin "36") (pinfunction "PB15_36") (pintype "bidirectional"))
      (node (ref "U2") (pin "35") (pinfunction "MOSI_35") (pintype "passive"))
    )
    (net (code "25") (name "ETH_RSTN") (class "Default")
      (node (ref "STM_CHIP") (pin "37") (pinfunction "PC6_37") (pintype "bidirectional"))
      (node (ref "U2") (pin "37") (pinfunction "RST_N_37") (pintype "passive"))
      (node (ref "W5500-R9") (pin "1") (pinfunction "1_1") (pintype "passive"))
    )
    (net (code "26") (name "ETH_SCK") (class "Default")
      (node (ref "STM_CHIP") (pin "34") (pinfunction "PB13_34") (pintype "bidirectional"))
      (node (ref "U2") (pin "33") (pinfunction "SCLK_33") (pintype "passive"))
    )
    (net (code "27") (name "F_CS") (class "Default")
      (node (ref "STM_CHIP") (pin "29") (pinfunction "PB10_29") (pintype "bidirectional"))
      (node (ref "U$4") (pin "F_CS") (pinfunction "F_CS_F_CS") (pintype "passive"))
    )
    (net (code "28") (name "GESP") (class "Default")
      (node (ref "ESP-C1") (pin "2") (pinfunction "2_2") (pintype "passive"))
      (node (ref "ESP-GND") (pin "2") (pinfunction "2_2") (pintype "passive"))
      (node (ref "ESP-GPIO0") (pin "3") (pinfunction "3_3") (pintype "passive"))
      (node (ref "ESP8266") (pin "GND") (pinfunction "GND_GND") (pintype "bidirectional"))
      (node (ref "ESP8266") (pin "GPIO15") (pinfunction "GPIO15_GPIO15") (pintype "bidirectional"))
    )
    (net (code "29") (name "GEXT") (class "Default")
      (node (ref "ESP-GND") (pin "3") (pinfunction "3_3") (pintype "passive"))
      (node (ref "ESP-UART-A") (pin "4") (pinfunction "4_4") (pintype "passive"))
    )
    (net (code "30") (name "LCD_CS") (class "Default")
      (node (ref "STM_CHIP") (pin "20") (pinfunction "PA4_20") (pintype "bidirectional"))
      (node (ref "U$4") (pin "LCD_CS") (pinfunction "LCD_CS_LCD_CS") (pintype "passive"))
    )
    (net (code "31") (name "LCD_D{slash}C") (class "Default")
      (node (ref "STM_CHIP") (pin "24") (pinfunction "PC4_24") (pintype "bidirectional"))
      (node (ref "U$4") (pin "LCD_D/C") (pinfunction "LCD_D/C_LCD_D/C") (pintype "passive"))
    )
    (net (code "32") (name "LCD_LED") (class "Default")
      (node (ref "LCD-R1") (pin "1") (pinfunction "1_1") (pintype "passive"))
      (node (ref "U$4") (pin "LCD_LED") (pinfunction "LCD_LED_LCD_LED") (pintype "passive"))
    )
    (net (code "33") (name "LCD_MISO") (class "Default")
      (node (ref "STM_CHIP") (pin "22") (pinfunction "PA6_22") (pintype "bidirectional"))
      (node (ref "U$4") (pin "LCD_MISO") (pinfunction "LCD_MISO_LCD_MISO") (pintype "passive"))
      (node (ref "U$4") (pin "SD_MISO") (pinfunction "SD_MISO_SD_MISO") (pintype "passive"))
    )
    (net (code "34") (name "LCD_MOSI") (class "Default")
      (node (ref "STM_CHIP") (pin "23") (pinfunction "PA7_23") (pintype "bidirectional"))
      (node (ref "U$4") (pin "LCD_MOSI") (pinfunction "LCD_MOSI_LCD_MOSI") (pintype "passive"))
      (node (ref "U$4") (pin "SD_MOSI") (pinfunction "SD_MOSI_SD_MOSI") (pintype "passive"))
    )
    (net (code "35") (name "LCD_RESET") (class "Default")
      (node (ref "STM_CHIP") (pin "25") (pinfunction "PC5_25") (pintype "bidirectional"))
      (node (ref "U$4") (pin "LCD_RESET") (pinfunction "LCD_RESET_LCD_RESET") (pintype "passive"))
    )
    (net (code "36") (name "LCD_SCK") (class "Default")
      (node (ref "STM_CHIP") (pin "21") (pinfunction "PA5_21") (pintype "bidirectional"))
      (node (ref "U$4") (pin "LCD_SCK") (pinfunction "LCD_SCK_LCD_SCK") (pintype "passive"))
      (node (ref "U$4") (pin "SD_SCK") (pinfunction "SD_SCK_SD_SCK") (pintype "passive"))
    )
    (net (code "37") (name "LINKLED") (class "Default")
      (node (ref "ETH-R5") (pin "1") (pinfunction "1_1") (pintype "passive"))
      (node (ref "U2") (pin "25") (pinfunction "LINKLED_25") (pintype "passive"))
    )
    (net (code "38") (name "MQ6_DATA") (class "Default")
      (node (ref "SENSOR-MQ7") (pin "B1") (pinfunction "B1_B1") (pintype "bidirectional"))
      (node (ref "STM_CHIP") (pin "26") (pinfunction "PB0_26") (pintype "bidirectional"))
    )
    (net (code "39") (name "MQ7_DATA") (class "Default")
      (node (ref "SENSOR-MQ6") (pin "B1") (pinfunction "B1_B1") (pintype "bidirectional"))
      (node (ref "STM_CHIP") (pin "27") (pinfunction "PB1_27") (pintype "bidirectional"))
    )
    (net (code "40") (name "Net-(ADE-R1-Pad1)") (class "Default")
      (node (ref "ADE-R1") (pin "1") (pinfunction "1_1") (pintype "passive"))
      (node (ref "VAC_IN1") (pin "PWR") (pinfunction "PWR_PWR") (pintype "bidirectional"))
    )
    (net (code "41") (name "Net-(ADE-R2-Pad1)") (class "Default")
      (node (ref "ADE-R2") (pin "1") (pinfunction "1_1") (pintype "passive"))
      (node (ref "VAC_IN2") (pin "PWR") (pinfunction "PWR_PWR") (pintype "bidirectional"))
    )
    (net (code "42") (name "Net-(ADE-R3-Pad1)") (class "Default")
      (node (ref "ADE-R3") (pin "1") (pinfunction "1_1") (pintype "passive"))
      (node (ref "VAC_IN3") (pin "PWR") (pinfunction "PWR_PWR") (pintype "bidirectional"))
    )
    (net (code "43") (name "Net-(ADE-R7-Pad1)") (class "Default")
      (node (ref "ADE-R7") (pin "1") (pinfunction "1_1") (pintype "passive"))
      (node (ref "VAC_IN1") (pin "GND") (pinfunction "GND_GND") (pintype "bidirectional"))
      (node (ref "VAC_IN1") (pin "GNDBREAK") (pinfunction "GNDBREAK_GNDBREAK") (pintype "bidirectional"))
      (node (ref "VAC_IN2") (pin "GND") (pinfunction "GND_GND") (pintype "bidirectional"))
      (node (ref "VAC_IN2") (pin "GNDBREAK") (pinfunction "GNDBREAK_GNDBREAK") (pintype "bidirectional"))
      (node (ref "VAC_IN3") (pin "GND") (pinfunction "GND_GND") (pintype "bidirectional"))
      (node (ref "VAC_IN3") (pin "GNDBREAK") (pinfunction "GNDBREAK_GNDBREAK") (pintype "bidirectional"))
    )
    (net (code "44") (name "Net-(ADE-R8-Pad2)") (class "Default")
      (node (ref "ADE-R8") (pin "2") (pinfunction "2_2") (pintype "passive"))
      (node (ref "ADE-R9") (pin "1") (pinfunction "1_1") (pintype "passive"))
      (node (ref "CT1") (pin "1") (pinfunction "1_1") (pintype "passive"))
    )
    (net (code "45") (name "Net-(ADE-R10-Pad1)") (class "Default")
      (node (ref "ADE-R10") (pin "1") (pinfunction "1_1") (pintype "passive"))
      (node (ref "ADE-R8") (pin "1") (pinfunction "1_1") (pintype "passive"))
      (node (ref "CT1") (pin "2") (pinfunction "2_2") (pintype "passive"))
      (node (ref "CT1") (pin "5") (pinfunction "5_5") (pintype "passive"))
    )
    (net (code "46") (name "Net-(ADE-R11-Pad1)") (class "Default")
      (node (ref "ADE-R11") (pin "1") (pinfunction "1_1") (pintype "passive"))
      (node (ref "ADE-R13") (pin "1") (pinfunction "1_1") (pintype "passive"))
      (node (ref "CT2") (pin "2") (pinfunction "2_2") (pintype "passive"))
      (node (ref "CT2") (pin "5") (pinfunction "5_5") (pintype "passive"))
    )
    (net (code "47") (name "Net-(ADE-R11-Pad2)") (class "Default")
      (node (ref "ADE-R11") (pin "2") (pinfunction "2_2") (pintype "passive"))
      (node (ref "ADE-R12") (pin "1") (pinfunction "1_1") (pintype "passive"))
      (node (ref "CT2") (pin "1") (pinfunction "1_1") (pintype "passive"))
    )
    (net (code "48") (name "Net-(ADE-R14-Pad1)") (class "Default")
      (node (ref "ADE-R14") (pin "1") (pinfunction "1_1") (pintype "passive"))
      (node (ref "ADE-R16") (pin "1") (pinfunction "1_1") (pintype "passive"))
      (node (ref "CT3") (pin "2") (pinfunction "2_2") (pintype "passive"))
      (node (ref "CT3") (pin "5") (pinfunction "5_5") (pintype "passive"))
    )
    (net (code "49") (name "Net-(ADE-R14-Pad2)") (class "Default")
      (node (ref "ADE-R14") (pin "2") (pinfunction "2_2") (pintype "passive"))
      (node (ref "ADE-R15") (pin "1") (pinfunction "1_1") (pintype "passive"))
      (node (ref "CT3") (pin "1") (pinfunction "1_1") (pintype "passive"))
    )
    (net (code "50") (name "Net-(ETHERNET-LED1_K)") (class "Default")
      (node (ref "ETH-R4") (pin "2") (pinfunction "2_2") (pintype "passive"))
      (node (ref "ETHERNET") (pin "10") (pinfunction "LED1_K_10") (pintype "bidirectional"))
    )
    (net (code "51") (name "Net-(ETHERNET-LED2_K)") (class "Default")
      (node (ref "ETH-R5") (pin "2") (pinfunction "2_2") (pintype "passive"))
      (node (ref "ETHERNET") (pin "11") (pinfunction "LED2_K_11") (pintype "bidirectional"))
    )
    (net (code "52") (name "Net-(ETHERNET-RCT)") (class "Default")
      (node (ref "ETH-C3") (pin "2") (pinfunction "2_2") (pintype "passive"))
      (node (ref "ETH-R6") (pin "1") (pinfunction "1_1") (pintype "passive"))
      (node (ref "ETH-R7") (pin "2") (pinfunction "2_2") (pintype "passive"))
      (node (ref "ETHERNET") (pin "6") (pinfunction "RCT_6") (pintype "bidirectional"))
    )
    (net (code "53") (name "Net-(ETHERNET-RX+)") (class "Default")
      (node (ref "ETH-C2") (pin "1") (pinfunction "1_1") (pintype "passive"))
      (node (ref "ETHERNET") (pin "7") (pinfunction "RX+_7") (pintype "bidirectional"))
    )
    (net (code "54") (name "Net-(ETHERNET-RX-)") (class "Default")
      (node (ref "ETH-C4") (pin "1") (pinfunction "1_1") (pintype "passive"))
      (node (ref "ETHERNET") (pin "8") (pinfunction "RX-_8") (pintype "bidirectional"))
    )
    (net (code "55") (name "Net-(ETHERNET-TCT)") (class "Default")
      (node (ref "ETH-C1") (pin "2") (pinfunction "2_2") (pintype "passive"))
      (node (ref "ETH-R3") (pin "1") (pinfunction "1_1") (pintype "passive"))
      (node (ref "ETHERNET") (pin "3") (pinfunction "TCT_3") (pintype "bidirectional"))
    )
    (net (code "56") (name "Net-(IC1-RF_ANT)") (class "Default")
      (node (ref "IC1") (pin "P$60") (pinfunction "RF_ANT_P$60") (pintype "bidirectional"))
      (node (ref "SIM900-ANT") (pin "ANTENNA") (pinfunction "ANT_ANTENNA") (pintype "bidirectional"))
    )
    (net (code "57") (name "Net-(IC1-SIM_CLK)") (class "Default")
      (node (ref "IC1") (pin "P$32") (pinfunction "SIM_CLK_P$32") (pintype "bidirectional"))
      (node (ref "SIM900-R2") (pin "1") (pinfunction "1_1") (pintype "passive"))
    )
    (net (code "58") (name "Net-(IC1-SIM_DATA)") (class "Default")
      (node (ref "IC1") (pin "P$31") (pinfunction "SIM_DATA_P$31") (pintype "bidirectional"))
      (node (ref "SIM900-R3") (pin "1") (pinfunction "1_1") (pintype "passive"))
    )
    (net (code "59") (name "Net-(IC1-SIM_RST)") (class "Default")
      (node (ref "IC1") (pin "P$33") (pinfunction "SIM_RST_P$33") (pintype "bidirectional"))
      (node (ref "SIM900-R1") (pin "1") (pinfunction "1_1") (pintype "passive"))
    )
    (net (code "60") (name "Net-(IC1-VRTC)") (class "Default")
      (node (ref "IC1") (pin "P$26") (pinfunction "VRTC_P$26") (pintype "power_in"))
      (node (ref "SIM900-C3") (pin "1") (pinfunction "1_1") (pintype "passive"))
    )
    (net (code "61") (name "Net-(IC4A-CLKIN)") (class "Default")
      (node (ref "ADE-C3") (pin "1") (pinfunction "1_1") (pintype "passive"))
      (node (ref "ADE-XTAL") (pin "1") (pinfunction "1_1") (pintype "passive"))
      (node (ref "IC4") (pin "19") (pinfunction "CLKIN_19") (pintype "input"))
    )
    (net (code "62") (name "Net-(IC4A-CLKOUT)") (class "Default")
      (node (ref "ADE-C4") (pin "1") (pinfunction "1_1") (pintype "passive"))
      (node (ref "ADE-XTAL") (pin "2") (pinfunction "2_2") (pintype "passive"))
      (node (ref "IC4") (pin "20") (pinfunction "CLKOUT_20") (pintype "output"))
    )
    (net (code "63") (name "Net-(IC4C-IN)") (class "Default")
      (node (ref "ADE-C12") (pin "1") (pinfunction "1_1") (pintype "passive"))
      (node (ref "ADE-R10") (pin "2") (pinfunction "2_2") (pintype "passive"))
      (node (ref "IC4") (pin "6") (pinfunction "IN_6") (pintype "input"))
    )
    (net (code "64") (name "Net-(IC4C-IP)") (class "Default")
      (node (ref "ADE-C11") (pin "1") (pinfunction "1_1") (pintype "passive"))
      (node (ref "ADE-R9") (pin "2") (pinfunction "2_2") (pintype "passive"))
      (node (ref "IC4") (pin "5") (pinfunction "IP_5") (pintype "input"))
    )
    (net (code "65") (name "Net-(IC4D-IN)") (class "Default")
      (node (ref "ADE-C14") (pin "1") (pinfunction "1_1") (pintype "passive"))
      (node (ref "ADE-R13") (pin "2") (pinfunction "2_2") (pintype "passive"))
      (node (ref "IC4") (pin "8") (pinfunction "IN_8") (pintype "input"))
    )
    (net (code "66") (name "Net-(IC4D-IP)") (class "Default")
      (node (ref "ADE-C13") (pin "1") (pinfunction "1_1") (pintype "passive"))
      (node (ref "ADE-R12") (pin "2") (pinfunction "2_2") (pintype "passive"))
      (node (ref "IC4") (pin "7") (pinfunction "IP_7") (pintype "input"))
    )
    (net (code "67") (name "Net-(IC4E-IN)") (class "Default")
      (node (ref "ADE-C16") (pin "1") (pinfunction "1_1") (pintype "passive"))
      (node (ref "ADE-R16") (pin "2") (pinfunction "2_2") (pintype "passive"))
      (node (ref "IC4") (pin "10") (pinfunction "IN_10") (pintype "input"))
    )
    (net (code "68") (name "Net-(IC4E-IP)") (class "Default")
      (node (ref "ADE-C15") (pin "1") (pinfunction "1_1") (pintype "passive"))
      (node (ref "ADE-R15") (pin "2") (pinfunction "2_2") (pintype "passive"))
      (node (ref "IC4") (pin "9") (pinfunction "IP_9") (pintype "input"))
    )
    (net (code "69") (name "Net-(IC4F-REF)") (class "Default")
      (node (ref "ADE-C1") (pin "1") (pinfunction "1_1") (pintype "passive"))
      (node (ref "ADE-C2") (pin "1") (pinfunction "1_1") (pintype "passive"))
      (node (ref "IC4") (pin "12") (pinfunction "REF_12") (pintype "bidirectional"))
    )
    (net (code "70") (name "Net-(IC4G-VAP)") (class "Default")
      (node (ref "ADE-C7") (pin "1") (pinfunction "1_1") (pintype "passive"))
      (node (ref "ADE-R1") (pin "2") (pinfunction "2_2") (pintype "passive"))
      (node (ref "ADE-R4") (pin "2") (pinfunction "2_2") (pintype "passive"))
      (node (ref "IC4") (pin "16") (pinfunction "VAP_16") (pintype "input"))
    )
    (net (code "71") (name "Net-(IC4G-VBP)") (class "Default")
      (node (ref "ADE-C8") (pin "1") (pinfunction "1_1") (pintype "passive"))
      (node (ref "ADE-R2") (pin "2") (pinfunction "2_2") (pintype "passive"))
      (node (ref "ADE-R5") (pin "2") (pinfunction "2_2") (pintype "passive"))
      (node (ref "IC4") (pin "15") (pinfunction "VBP_15") (pintype "input"))
    )
    (net (code "72") (name "Net-(IC4G-VCP)") (class "Default")
      (node (ref "ADE-C9") (pin "1") (pinfunction "1_1") (pintype "passive"))
      (node (ref "ADE-R3") (pin "2") (pinfunction "2_2") (pintype "passive"))
      (node (ref "ADE-R6") (pin "2") (pinfunction "2_2") (pintype "passive"))
      (node (ref "IC4") (pin "14") (pinfunction "VCP_14") (pintype "input"))
    )
    (net (code "73") (name "Net-(IC4G-VN)") (class "Default")
      (node (ref "ADE-C10") (pin "1") (pinfunction "1_1") (pintype "passive"))
      (node (ref "ADE-R7") (pin "2") (pinfunction "2_2") (pintype "passive"))
      (node (ref "IC4") (pin "13") (pinfunction "VN_13") (pintype "input"))
    )
    (net (code "74") (name "Net-(MQ6-R1-Pad2)") (class "Default")
      (node (ref "MQ6-R1") (pin "2") (pinfunction "2_2") (pintype "passive"))
      (node (ref "SENSOR-MQ6") (pin "B2") (pinfunction "B2_B2") (pintype "bidirectional"))
    )
    (net (code "75") (name "Net-(MQ7-R1-Pad2)") (class "Default")
      (node (ref "MQ7-R1") (pin "2") (pinfunction "2_2") (pintype "passive"))
      (node (ref "SENSOR-MQ7") (pin "B2") (pinfunction "B2_B2") (pintype "bidirectional"))
    )
    (net (code "76") (name "Net-(SIM900-LED1-PadA)") (class "Default")
      (node (ref "SIM900-LED1") (pin "A") (pinfunction "A_A") (pintype "passive"))
      (node (ref "SIM900-R4") (pin "1") (pinfunction "1_1") (pintype "passive"))
    )
    (net (code "77") (name "Net-(SIM900-LED1-PadC)") (class "Default")
      (node (ref "SIM900-LED1") (pin "C") (pinfunction "C_C") (pintype "passive"))
      (node (ref "SIM900-T1") (pin "C") (pinfunction "C_C") (pintype "passive"))
    )
    (net (code "78") (name "Net-(SIM900-LED2-PadA)") (class "Default")
      (node (ref "SIM900-LED2") (pin "A") (pinfunction "A_A") (pintype "passive"))
      (node (ref "SIM900-R7") (pin "1") (pinfunction "1_1") (pintype "passive"))
    )
    (net (code "79") (name "Net-(SIM900-LED2-PadC)") (class "Default")
      (node (ref "SIM900-LED2") (pin "C") (pinfunction "C_C") (pintype "passive"))
      (node (ref "SIM900-T2") (pin "C") (pinfunction "C_C") (pintype "passive"))
    )
    (net (code "80") (name "Net-(SIM900-R5-Pad1)") (class "Default")
      (node (ref "SIM900-R5") (pin "1") (pinfunction "1_1") (pintype "passive"))
      (node (ref "SIM900-R6") (pin "1") (pinfunction "1_1") (pintype "passive"))
      (node (ref "SIM900-T1") (pin "B") (pinfunction "B_B") (pintype "passive"))
    )
    (net (code "81") (name "Net-(SIM900-R8-Pad1)") (class "Default")
      (node (ref "SIM900-R8") (pin "1") (pinfunction "1_1") (pintype "passive"))
      (node (ref "SIM900-R9") (pin "1") (pinfunction "1_1") (pintype "passive"))
      (node (ref "SIM900-T2") (pin "B") (pinfunction "B_B") (pintype "passive"))
    )
    (net (code "82") (name "Net-(SIM900-R10-Pad2)") (class "Default")
      (node (ref "SIM900-R10") (pin "2") (pinfunction "2_2") (pintype "passive"))
      (node (ref "SIM900-T3") (pin "B") (pinfunction "B_B") (pintype "passive"))
    )
    (net (code "83") (name "Net-(SIM900-R11-Pad2)") (class "Default")
      (node (ref "SIM900-R11") (pin "2") (pinfunction "2_2") (pintype "passive"))
      (node (ref "SIM900-T4") (pin "B") (pinfunction "B_B") (pintype "passive"))
    )
    (net (code "84") (name "Net-(STM-HD1-Pad2)") (class "Default")
      (node (ref "STM-HD1") (pin "2") (pinfunction "2_2") (pintype "passive"))
      (node (ref "STM-R4") (pin "2") (pinfunction "2_2") (pintype "passive"))
    )
    (net (code "85") (name "Net-(STM-HD2-Pad2)") (class "Default")
      (node (ref "STM-HD2") (pin "2") (pinfunction "2_2") (pintype "passive"))
      (node (ref "STM-R5") (pin "2") (pinfunction "2_2") (pintype "passive"))
    )
    (net (code "86") (name "Net-(STM_CHIP-PC14-OSC32_IN)") (class "Default")
      (node (ref "STM-C2") (pin "2") (pinfunction "2_2") (pintype "passive"))
      (node (ref "STM-XTAL") (pin "2") (pinfunction "2_2") (pintype "passive"))
      (node (ref "STM_CHIP") (pin "3") (pinfunction "PC14-OSC32_IN_3") (pintype "bidirectional"))
    )
    (net (code "87") (name "Net-(STM_CHIP-PC15-OSC32_OUT)") (class "Default")
      (node (ref "STM-C3") (pin "2") (pinfunction "2_2") (pintype "passive"))
      (node (ref "STM-XTAL") (pin "1") (pinfunction "1_1") (pintype "passive"))
      (node (ref "STM_CHIP") (pin "4") (pinfunction "PC15-OSC32_OUT_4") (pintype "bidirectional"))
    )
    (net (code "88") (name "Net-(U2-1V2O)") (class "Default")
      (node (ref "U2") (pin "22") (pinfunction "1V2O_22") (pintype "passive"))
      (node (ref "W5500-C4") (pin "1") (pinfunction "1_1") (pintype "passive"))
    )
    (net (code "89") (name "Net-(U2-EXRES1)") (class "Default")
      (node (ref "U2") (pin "10") (pinfunction "EXRES1_10") (pintype "passive"))
      (node (ref "W5500-R12") (pin "2") (pinfunction "2_2") (pintype "passive"))
    )
    (net (code "90") (name "Net-(U2-PMODE0)") (class "Default")
      (node (ref "U2") (pin "45") (pinfunction "PMODE0_45") (pintype "passive"))
      (node (ref "W5500-R3") (pin "2") (pinfunction "2_2") (pintype "passive"))
    )
    (net (code "91") (name "Net-(U2-PMODE1)") (class "Default")
      (node (ref "U2") (pin "44") (pinfunction "PMODE1_44") (pintype "passive"))
      (node (ref "W5500-R2") (pin "2") (pinfunction "2_2") (pintype "passive"))
    )
    (net (code "92") (name "Net-(U2-PMODE2)") (class "Default")
      (node (ref "U2") (pin "43") (pinfunction "PMODE2_43") (pintype "passive"))
      (node (ref "W5500-R1") (pin "2") (pinfunction "2_2") (pintype "passive"))
    )
    (net (code "93") (name "Net-(U2-RSVD-Pad23)") (class "Default")
      (node (ref "U2") (pin "23") (pinfunction "RSVD_23") (pintype "passive"))
      (node (ref "W5500-R11") (pin "2") (pinfunction "2_2") (pintype "passive"))
    )
    (net (code "94") (name "Net-(U2-RSVD-Pad38)") (class "Default")
      (node (ref "U2") (pin "38") (pinfunction "RSVD_38") (pintype "passive"))
      (node (ref "W5500-R8") (pin "1") (pinfunction "1_1") (pintype "passive"))
    )
    (net (code "95") (name "Net-(U2-RSVD-Pad39)") (class "Default")
      (node (ref "U2") (pin "39") (pinfunction "RSVD_39") (pintype "passive"))
      (node (ref "W5500-R7") (pin "1") (pinfunction "1_1") (pintype "passive"))
    )
    (net (code "96") (name "Net-(U2-RSVD-Pad40)") (class "Default")
      (node (ref "U2") (pin "40") (pinfunction "RSVD_40") (pintype "passive"))
      (node (ref "W5500-R6") (pin "1") (pinfunction "1_1") (pintype "passive"))
    )
    (net (code "97") (name "Net-(U2-RSVD-Pad41)") (class "Default")
      (node (ref "U2") (pin "41") (pinfunction "RSVD_41") (pintype "passive"))
      (node (ref "W5500-R5") (pin "1") (pinfunction "1_1") (pintype "passive"))
    )
    (net (code "98") (name "Net-(U2-RSVD-Pad42)") (class "Default")
      (node (ref "U2") (pin "42") (pinfunction "RSVD_42") (pintype "passive"))
      (node (ref "W5500-R4") (pin "1") (pinfunction "1_1") (pintype "passive"))
    )
    (net (code "99") (name "Net-(U2-TOCAP)") (class "Default")
      (node (ref "U2") (pin "20") (pinfunction "TOCAP_20") (pintype "passive"))
      (node (ref "W5500-C3") (pin "1") (pinfunction "1_1") (pintype "passive"))
    )
    (net (code "100") (name "Net-(U2-XI{slash}CLKIN)") (class "Default")
      (node (ref "U$3") (pin "P$1") (pinfunction "P$1_P$1") (pintype "bidirectional"))
      (node (ref "U2") (pin "30") (pinfunction "XI/CLKIN_30") (pintype "passive"))
      (node (ref "W5500-C1") (pin "1") (pinfunction "1_1") (pintype "passive"))
      (node (ref "W5500-R10") (pin "1") (pinfunction "1_1") (pintype "passive"))
      (node (ref "W5500-XTAL") (pin "1") (pinfunction "1_1") (pintype "passive"))
    )
    (net (code "101") (name "Net-(U2-XO)") (class "Default")
      (node (ref "U$3") (pin "P$2") (pinfunction "P$2_P$2") (pintype "bidirectional"))
      (node (ref "U2") (pin "31") (pinfunction "XO_31") (pintype "passive"))
      (node (ref "W5500-C2") (pin "1") (pinfunction "1_1") (pintype "passive"))
      (node (ref "W5500-R10") (pin "2") (pinfunction "2_2") (pintype "passive"))
      (node (ref "W5500-XTAL") (pin "2") (pinfunction "2_2") (pintype "passive"))
    )
    (net (code "102") (name "Q1") (class "Default")
      (node (ref "IC2") (pin "15") (pinfunction "QA_15") (pintype "tri_state"))
      (node (ref "SR_OUT1") (pin "3") (pinfunction "3_3") (pintype "passive"))
    )
    (net (code "103") (name "Q2") (class "Default")
      (node (ref "IC2") (pin "1") (pinfunction "QB_1") (pintype "tri_state"))
      (node (ref "SR_OUT1") (pin "4") (pinfunction "4_4") (pintype "passive"))
    )
    (net (code "104") (name "Q3") (class "Default")
      (node (ref "IC2") (pin "2") (pinfunction "QC_2") (pintype "tri_state"))
      (node (ref "SR_OUT1") (pin "5") (pinfunction "5_5") (pintype "passive"))
    )
    (net (code "105") (name "Q4") (class "Default")
      (node (ref "IC2") (pin "3") (pinfunction "QD_3") (pintype "tri_state"))
      (node (ref "SR_OUT1") (pin "6") (pinfunction "6_6") (pintype "passive"))
    )
    (net (code "106") (name "Q5") (class "Default")
      (node (ref "IC2") (pin "4") (pinfunction "QE_4") (pintype "tri_state"))
      (node (ref "SR_OUT1") (pin "7") (pinfunction "7_7") (pintype "passive"))
    )
    (net (code "107") (name "Q6") (class "Default")
      (node (ref "IC2") (pin "5") (pinfunction "QF_5") (pintype "tri_state"))
      (node (ref "SR_OUT1") (pin "8") (pinfunction "8_8") (pintype "passive"))
    )
    (net (code "108") (name "Q7") (class "Default")
      (node (ref "IC2") (pin "6") (pinfunction "QG_6") (pintype "tri_state"))
      (node (ref "SR_OUT1") (pin "9") (pinfunction "9_9") (pintype "passive"))
    )
    (net (code "109") (name "Q8") (class "Default")
      (node (ref "IC2") (pin "7") (pinfunction "QH_7") (pintype "tri_state"))
      (node (ref "SR_OUT1") (pin "10") (pinfunction "10_10") (pintype "passive"))
    )
    (net (code "110") (name "Q9") (class "Default")
      (node (ref "IC3") (pin "15") (pinfunction "QA_15") (pintype "tri_state"))
      (node (ref "SR_OUT2") (pin "3") (pinfunction "3_3") (pintype "passive"))
    )
    (net (code "111") (name "Q10") (class "Default")
      (node (ref "IC3") (pin "1") (pinfunction "QB_1") (pintype "tri_state"))
      (node (ref "SR_OUT2") (pin "4") (pinfunction "4_4") (pintype "passive"))
    )
    (net (code "112") (name "Q11") (class "Default")
      (node (ref "IC3") (pin "2") (pinfunction "QC_2") (pintype "tri_state"))
      (node (ref "SR_OUT2") (pin "5") (pinfunction "5_5") (pintype "passive"))
    )
    (net (code "113") (name "Q12") (class "Default")
      (node (ref "IC3") (pin "3") (pinfunction "QD_3") (pintype "tri_state"))
      (node (ref "SR_OUT2") (pin "6") (pinfunction "6_6") (pintype "passive"))
    )
    (net (code "114") (name "Q13") (class "Default")
      (node (ref "IC3") (pin "4") (pinfunction "QE_4") (pintype "tri_state"))
      (node (ref "SR_OUT2") (pin "7") (pinfunction "7_7") (pintype "passive"))
    )
    (net (code "115") (name "Q14") (class "Default")
      (node (ref "IC3") (pin "5") (pinfunction "QF_5") (pintype "tri_state"))
      (node (ref "SR_OUT2") (pin "8") (pinfunction "8_8") (pintype "passive"))
    )
    (net (code "116") (name "Q15") (class "Default")
      (node (ref "IC3") (pin "6") (pinfunction "QG_6") (pintype "tri_state"))
      (node (ref "SR_OUT2") (pin "9") (pinfunction "9_9") (pintype "passive"))
    )
    (net (code "117") (name "Q16") (class "Default")
      (node (ref "IC3") (pin "7") (pinfunction "QH_7") (pintype "tri_state"))
      (node (ref "SR_OUT2") (pin "10") (pinfunction "10_10") (pintype "passive"))
    )
    (net (code "118") (name "QS") (class "Default")
      (node (ref "IC2") (pin "9") (pinfunction "QH*_9") (pintype "tri_state"))
      (node (ref "IC3") (pin "14") (pinfunction "SER_14") (pintype "input"))
    )
    (net (code "119") (name "RXN") (class "Default")
      (node (ref "ETH-C4") (pin "2") (pinfunction "2_2") (pintype "passive"))
      (node (ref "ETH-R7") (pin "1") (pinfunction "1_1") (pintype "passive"))
      (node (ref "U2") (pin "5") (pinfunction "RXN_5") (pintype "passive"))
    )
    (net (code "120") (name "RXP") (class "Default")
      (node (ref "ETH-C2") (pin "2") (pinfunction "2_2") (pintype "passive"))
      (node (ref "ETH-R6") (pin "2") (pinfunction "2_2") (pintype "passive"))
      (node (ref "U2") (pin "6") (pinfunction "RXP_6") (pintype "passive"))
    )
    (net (code "121") (name "SD_CS") (class "Default")
      (node (ref "STM_CHIP") (pin "53") (pinfunction "PC12_53") (pintype "bidirectional"))
      (node (ref "U$4") (pin "SD_CS") (pinfunction "SD_CS_SD_CS") (pintype "passive"))
    )
    (net (code "122") (name "SERIAL_RX") (class "Default")
      (node (ref "STM-USART") (pin "3") (pinfunction "3_3") (pintype "passive"))
      (node (ref "STM_CHIP") (pin "43") (pinfunction "PA10_43") (pintype "bidirectional"))
    )
    (net (code "123") (name "SERIAL_TX") (class "Default")
      (node (ref "STM-USART") (pin "2") (pinfunction "2_2") (pintype "passive"))
      (node (ref "STM_CHIP") (pin "42") (pinfunction "PA9_42") (pintype "bidirectional"))
    )
    (net (code "124") (name "SIM900_PWRKEY") (class "Default")
      (node (ref "IC1") (pin "P$1") (pinfunction "PWRKEY_P$1") (pintype "power_in"))
      (node (ref "SIM900-T3") (pin "C") (pinfunction "C_C") (pintype "passive"))
    )
    (net (code "125") (name "SIM900_RESET") (class "Default")
      (node (ref "IC1") (pin "P$16") (pinfunction "NRESET_P$16") (pintype "bidirectional"))
      (node (ref "SIM900-T4") (pin "C") (pinfunction "C_C") (pintype "passive"))
    )
    (net (code "126") (name "SIM_NETLIGHT") (class "Default")
      (node (ref "IC1") (pin "P$52") (pinfunction "NETLIGHT_P$52") (pintype "bidirectional"))
      (node (ref "SIM900-R8") (pin "2") (pinfunction "2_2") (pintype "passive"))
    )
    (net (code "127") (name "SIM_PWRKEY") (class "Default")
      (node (ref "SIM900-R10") (pin "1") (pinfunction "1_1") (pintype "passive"))
      (node (ref "STM_CHIP") (pin "40") (pinfunction "PC9_40") (pintype "bidirectional"))
    )
    (net (code "128") (name "SIM_RESET") (class "Default")
      (node (ref "SIM900-R11") (pin "1") (pinfunction "1_1") (pintype "passive"))
      (node (ref "STM_CHIP") (pin "50") (pinfunction "PA15_50") (pintype "bidirectional"))
    )
    (net (code "129") (name "SIM_RX") (class "Default")
      (node (ref "IC1") (pin "P$10") (pinfunction "RXD_P$10") (pintype "input"))
      (node (ref "STM_CHIP") (pin "51") (pinfunction "PC10_51") (pintype "bidirectional"))
    )
    (net (code "130") (name "SIM_STATUS") (class "Default")
      (node (ref "IC1") (pin "P$66") (pinfunction "STATUS_P$66") (pintype "bidirectional"))
      (node (ref "SIM900-R5") (pin "2") (pinfunction "2_2") (pintype "passive"))
    )
    (net (code "131") (name "SIM_TX") (class "Default")
      (node (ref "IC1") (pin "P$9") (pinfunction "TXD_P$9") (pintype "output"))
      (node (ref "STM_CHIP") (pin "52") (pinfunction "PC11_52") (pintype "bidirectional"))
    )
    (net (code "132") (name "SR_DS") (class "Default")
      (node (ref "IC2") (pin "14") (pinfunction "SER_14") (pintype "input"))
      (node (ref "STM_CHIP") (pin "8") (pinfunction "PC0_8") (pintype "bidirectional"))
    )
    (net (code "133") (name "SR_RST") (class "Default")
      (node (ref "IC2") (pin "10") (pinfunction "SCL_10") (pintype "input"))
      (node (ref "IC3") (pin "10") (pinfunction "SCL_10") (pintype "input"))
      (node (ref "STM_CHIP") (pin "11") (pinfunction "PC3_11") (pintype "bidirectional"))
    )
    (net (code "134") (name "SR_SHCP") (class "Default")
      (node (ref "IC2") (pin "11") (pinfunction "SCK_11") (pintype "input"))
      (node (ref "IC3") (pin "11") (pinfunction "SCK_11") (pintype "input"))
      (node (ref "STM_CHIP") (pin "10") (pinfunction "PC2_10") (pintype "bidirectional"))
    )
    (net (code "135") (name "SR_STCP") (class "Default")
      (node (ref "IC2") (pin "12") (pinfunction "RCK_12") (pintype "input"))
      (node (ref "IC3") (pin "12") (pinfunction "RCK_12") (pintype "input"))
      (node (ref "STM_CHIP") (pin "9") (pinfunction "PC1_9") (pintype "bidirectional"))
    )
    (net (code "136") (name "SWD_NRST") (class "Default")
      (node (ref "S1") (pin "1") (pinfunction "1_1") (pintype "passive"))
      (node (ref "S1") (pin "2") (pinfunction "2_2") (pintype "passive"))
      (node (ref "STM-C8") (pin "1") (pinfunction "1_1") (pintype "passive"))
      (node (ref "STM_CHIP") (pin "7") (pinfunction "NRST_7") (pintype "bidirectional"))
    )
    (net (code "137") (name "SWD_TCK") (class "Default")
      (node (ref "STM-SWD") (pin "2") (pinfunction "2_2") (pintype "passive"))
      (node (ref "STM_CHIP") (pin "49") (pinfunction "PA14_49") (pintype "bidirectional"))
    )
    (net (code "138") (name "SWD_TMS") (class "Default")
      (node (ref "STM-SWD") (pin "4") (pinfunction "4_4") (pintype "passive"))
      (node (ref "STM_CHIP") (pin "46") (pinfunction "PA13_46") (pintype "bidirectional"))
    )
    (net (code "139") (name "TXN") (class "Default")
      (node (ref "ETH-R2") (pin "1") (pinfunction "1_1") (pintype "passive"))
      (node (ref "ETHERNET") (pin "2") (pinfunction "TX-_2") (pintype "bidirectional"))
      (node (ref "U2") (pin "1") (pinfunction "TXN_1") (pintype "passive"))
    )
    (net (code "140") (name "TXP") (class "Default")
      (node (ref "ETH-R1") (pin "1") (pinfunction "1_1") (pintype "passive"))
      (node (ref "ETHERNET") (pin "1") (pinfunction "TX+_1") (pintype "bidirectional"))
      (node (ref "U2") (pin "2") (pinfunction "TXP_2") (pintype "passive"))
    )
    (net (code "141") (name "USIM_CLK") (class "Default")
      (node (ref "SIM900-R2") (pin "2") (pinfunction "2_2") (pintype "passive"))
      (node (ref "SIM_HOLDER") (pin "3") (pinfunction "CLK_3") (pintype "bidirectional"))
    )
    (net (code "142") (name "USIM_DATA") (class "Default")
      (node (ref "SIM900-R3") (pin "2") (pinfunction "2_2") (pintype "passive"))
      (node (ref "SIM_HOLDER") (pin "4") (pinfunction "I/O_4") (pintype "bidirectional"))
    )
    (net (code "143") (name "USIM_RESET") (class "Default")
      (node (ref "SIM900-R1") (pin "2") (pinfunction "2_2") (pintype "passive"))
      (node (ref "SIM_HOLDER") (pin "2") (pinfunction "RST_2") (pintype "bidirectional"))
    )
    (net (code "144") (name "USIM_VCC") (class "Default")
      (node (ref "IC1") (pin "P$30") (pinfunction "SIM_VDD_P$30") (pintype "power_in"))
      (node (ref "SIM900-C4") (pin "1") (pinfunction "1_1") (pintype "passive"))
      (node (ref "SIM900-C5") (pin "1") (pinfunction "1_1") (pintype "passive"))
      (node (ref "SIM_C1") (pin "2") (pinfunction "2_2") (pintype "passive"))
      (node (ref "SIM_C2") (pin "2") (pinfunction "2_2") (pintype "passive"))
      (node (ref "SIM_HOLDER") (pin "1") (pinfunction "VCC_1") (pintype "bidirectional"))
    )
    (net (code "145") (name "VBAT") (class "Default")
      (node (ref "BAT1") (pin "1") (pinfunction "+_1") (pintype "power_in"))
      (node (ref "STM_CHIP") (pin "1") (pinfunction "VLCD_1") (pintype "power_in"))
    )
    (net (code "146") (name "VCC") (class "Default")
      (node (ref "ETH-R1") (pin "2") (pinfunction "2_2") (pintype "passive"))
      (node (ref "ETH-R2") (pin "2") (pinfunction "2_2") (pintype "passive"))
      (node (ref "ETH-R3") (pin "2") (pinfunction "2_2") (pintype "passive"))
      (node (ref "STM-C9") (pin "1") (pinfunction "1_1") (pintype "passive"))
      (node (ref "STM-L1") (pin "2") (pinfunction "2_2") (pintype "passive"))
      (node (ref "STM_CHIP") (pin "13") (pinfunction "VDDA_13") (pintype "power_in"))
      (node (ref "SYS-C4") (pin "1") (pinfunction "1_1") (pintype "passive"))
      (node (ref "SYS-R2") (pin "2") (pinfunction "2_2") (pintype "passive"))
      (node (ref "U2") (pin "11") (pinfunction "AVDD_11") (pintype "passive"))
      (node (ref "U2") (pin "15") (pinfunction "AVDD_15") (pintype "passive"))
      (node (ref "U2") (pin "17") (pinfunction "AVDD_17") (pintype "passive"))
      (node (ref "U2") (pin "21") (pinfunction "AVDD_21") (pintype "passive"))
      (node (ref "U2") (pin "4") (pinfunction "AVDD_4") (pintype "passive"))
      (node (ref "U2") (pin "8") (pinfunction "AVDD_8") (pintype "passive"))
      (node (ref "W5500-C10") (pin "1") (pinfunction "1_1") (pintype "passive"))
      (node (ref "W5500-C11") (pin "1") (pinfunction "1_1") (pintype "passive"))
      (node (ref "W5500-C12") (pin "+") (pinfunction "+_+") (pintype "passive"))
      (node (ref "W5500-C6") (pin "1") (pinfunction "1_1") (pintype "passive"))
      (node (ref "W5500-C7") (pin "1") (pinfunction "1_1") (pintype "passive"))
      (node (ref "W5500-C8") (pin "1") (pinfunction "1_1") (pintype "passive"))
      (node (ref "W5500-C9") (pin "1") (pinfunction "1_1") (pintype "passive"))
    )
    (net (code "147") (name "VDD") (class "Default")
      (node (ref "DHT-R1") (pin "1") (pinfunction "1_1") (pintype "passive"))
      (node (ref "ESP-VDD") (pin "1") (pinfunction "1_1") (pintype "passive"))
      (node (ref "ETHERNET") (pin "12") (pinfunction "LED2_A_12") (pintype "bidirectional"))
      (node (ref "ETHERNET") (pin "9") (pinfunction "LED1_A_9") (pintype "bidirectional"))
      (node (ref "IC1") (pin "P$55") (pinfunction "VBAT1_P$55") (pintype "power_in"))
      (node (ref "IC1") (pin "P$56") (pinfunction "VBAT2_P$56") (pintype "power_in"))
      (node (ref "IC1") (pin "P$57") (pinfunction "VBAT3_P$57") (pintype "power_in"))
      (node (ref "IC2") (pin "16") (pinfunction "VCC_16") (pintype "power_in"))
      (node (ref "IC3") (pin "16") (pinfunction "VCC_16") (pintype "power_in"))
      (node (ref "LCD-R1") (pin "2") (pinfunction "2_2") (pintype "passive"))
      (node (ref "PWR-SWT") (pin "1") (pinfunction "1_1") (pintype "passive"))
      (node (ref "SENSOR-DHT") (pin "1") (pinfunction "1_1") (pintype "passive"))
      (node (ref "SIM900-C1") (pin "+") (pinfunction "+_+") (pintype "passive"))
      (node (ref "SIM900-C2") (pin "+") (pinfunction "+_+") (pintype "passive"))
      (node (ref "SIM900-R4") (pin "2") (pinfunction "2_2") (pintype "passive"))
      (node (ref "SIM900-R7") (pin "2") (pinfunction "2_2") (pintype "passive"))
      (node (ref "STM-C1") (pin "2") (pinfunction "2_2") (pintype "passive"))
      (node (ref "STM-C10") (pin "1") (pinfunction "1_1") (pintype "passive"))
      (node (ref "STM-C11") (pin "1") (pinfunction "1_1") (pintype "passive"))
      (node (ref "STM-C12") (pin "1") (pinfunction "1_1") (pintype "passive"))
      (node (ref "STM-C13") (pin "1") (pinfunction "1_1") (pintype "passive"))
      (node (ref "STM-HD1") (pin "1") (pinfunction "1_1") (pintype "passive"))
      (node (ref "STM-HD2") (pin "1") (pinfunction "1_1") (pintype "passive"))
      (node (ref "STM-L1") (pin "1") (pinfunction "1_1") (pintype "passive"))
      (node (ref "STM-SWD") (pin "1") (pinfunction "1_1") (pintype "passive"))
      (node (ref "STM-USART") (pin "1") (pinfunction "1_1") (pintype "passive"))
      (node (ref "STM_CHIP") (pin "19") (pinfunction "VDD_4_19") (pintype "power_in"))
      (node (ref "STM_CHIP") (pin "32") (pinfunction "VDD_1_32") (pintype "power_in"))
      (node (ref "STM_CHIP") (pin "48") (pinfunction "VDD_2_48") (pintype "power_in"))
      (node (ref "STM_CHIP") (pin "64") (pinfunction "VDD_3_64") (pintype "power_in"))
      (node (ref "SYS-C3") (pin "1") (pinfunction "1_1") (pintype "passive"))
      (node (ref "SYS-R2") (pin "1") (pinfunction "1_1") (pintype "passive"))
      (node (ref "U$4") (pin "LCD_VCC") (pinfunction "LCD_VCC_LCD_VCC") (pintype "passive"))
      (node (ref "U2") (pin "28") (pinfunction "VDD_28") (pintype "passive"))
      (node (ref "W5500-C13") (pin "+") (pinfunction "+_+") (pintype "passive"))
      (node (ref "W5500-C5") (pin "1") (pinfunction "1_1") (pintype "passive"))
      (node (ref "W5500-R1") (pin "1") (pinfunction "1_1") (pintype "passive"))
      (node (ref "W5500-R13") (pin "2") (pinfunction "2_2") (pintype "passive"))
      (node (ref "W5500-R2") (pin "1") (pinfunction "1_1") (pintype "passive"))
      (node (ref "W5500-R3") (pin "1") (pinfunction "1_1") (pintype "passive"))
      (node (ref "W5500-R9") (pin "2") (pinfunction "2_2") (pintype "passive"))
    )
    (net (code "148") (name "VESP") (class "Default")
      (node (ref "ESP-C1") (pin "1") (pinfunction "1_1") (pintype "passive"))
      (node (ref "ESP-GPIO0") (pin "1") (pinfunction "1_1") (pintype "passive"))
      (node (ref "ESP-VDD") (pin "2") (pinfunction "2_2") (pintype "passive"))
      (node (ref "ESP8266") (pin "CH_PD") (pinfunction "CH_PD_CH_PD") (pintype "bidirectional"))
      (node (ref "ESP8266") (pin "VCC") (pinfunction "VCC_VCC") (pintype "bidirectional"))
    )
    (net (code "149") (name "VEXT") (class "Default")
      (node (ref "ESP-UART-A") (pin "1") (pinfunction "1_1") (pintype "passive"))
      (node (ref "ESP-VDD") (pin "3") (pinfunction "3_3") (pintype "passive"))
    )
    (net (code "150") (name "unconnected-(CT1-Pad3)") (class "Default")
      (node (ref "CT1") (pin "3") (pinfunction "3_3") (pintype "passive"))
    )
    (net (code "151") (name "unconnected-(CT1-Pad4)") (class "Default")
      (node (ref "CT1") (pin "4") (pinfunction "4_4") (pintype "passive"))
    )
    (net (code "152") (name "unconnected-(CT2-Pad3)") (class "Default")
      (node (ref "CT2") (pin "3") (pinfunction "3_3") (pintype "passive"))
    )
    (net (code "153") (name "unconnected-(CT2-Pad4)") (class "Default")
      (node (ref "CT2") (pin "4") (pinfunction "4_4") (pintype "passive"))
    )
    (net (code "154") (name "unconnected-(CT3-Pad3)") (class "Default")
      (node (ref "CT3") (pin "3") (pinfunction "3_3") (pintype "passive"))
    )
    (net (code "155") (name "unconnected-(CT3-Pad4)") (class "Default")
      (node (ref "CT3") (pin "4") (pinfunction "4_4") (pintype "passive"))
    )
    (net (code "156") (name "unconnected-(ESP8266-PadGPIO2)") (class "Default")
      (node (ref "ESP8266") (pin "GPIO2") (pinfunction "GPIO2_GPIO2") (pintype "bidirectional"))
    )
    (net (code "157") (name "unconnected-(ESP8266-PadGPIO11)") (class "Default")
      (node (ref "ESP8266") (pin "GPIO11") (pinfunction "GPIO11_GPIO11") (pintype "bidirectional"))
    )
    (net (code "158") (name "unconnected-(ESP8266-PadGPIO12)") (class "Default")
      (node (ref "ESP8266") (pin "GPIO12") (pinfunction "GPIO12_GPIO12") (pintype "bidirectional"))
    )
    (net (code "159") (name "unconnected-(ESP8266-PadGPIO13)") (class "Default")
      (node (ref "ESP8266") (pin "GPIO13") (pinfunction "GPIO13_GPIO13") (pintype "bidirectional"))
    )
    (net (code "160") (name "unconnected-(ESP8266-PadGPIO16)") (class "Default")
      (node (ref "ESP8266") (pin "GPIO16") (pinfunction "GPIO16_GPIO16") (pintype "bidirectional"))
    )
    (net (code "161") (name "unconnected-(ESP8266-PadNC)") (class "Default")
      (node (ref "ESP8266") (pin "NC") (pinfunction "NC_NC") (pintype "bidirectional"))
    )
    (net (code "162") (name "unconnected-(ESP8266-WIFI_ANT-PadANT)") (class "Default")
      (node (ref "ESP8266") (pin "ANT") (pinfunction "WIFI_ANT_ANT") (pintype "bidirectional"))
    )
    (net (code "163") (name "unconnected-(IC1-ADC-PadP$25)") (class "Default")
      (node (ref "IC1") (pin "P$25") (pinfunction "ADC_P$25") (pintype "bidirectional"))
    )
    (net (code "164") (name "unconnected-(IC1-CTS-PadP$7)") (class "Default")
      (node (ref "IC1") (pin "P$7") (pinfunction "CTS_P$7") (pintype "output"))
    )
    (net (code "165") (name "unconnected-(IC1-DBG_RXD-PadP$28)") (class "Default")
      (node (ref "IC1") (pin "P$28") (pinfunction "DBG_RXD_P$28") (pintype "input"))
    )
    (net (code "166") (name "unconnected-(IC1-DBG_TXD-PadP$27)") (class "Default")
      (node (ref "IC1") (pin "P$27") (pinfunction "DBG_TXD_P$27") (pintype "output"))
    )
    (net (code "167") (name "unconnected-(IC1-DCD-PadP$5)") (class "Default")
      (node (ref "IC1") (pin "P$5") (pinfunction "DCD_P$5") (pintype "output"))
    )
    (net (code "168") (name "unconnected-(IC1-DISP_CLK-PadP$11)") (class "Default")
      (node (ref "IC1") (pin "P$11") (pinfunction "DISP_CLK_P$11") (pintype "bidirectional"))
    )
    (net (code "169") (name "unconnected-(IC1-DISP_CS-PadP$14)") (class "Default")
      (node (ref "IC1") (pin "P$14") (pinfunction "DISP_CS_P$14") (pintype "bidirectional"))
    )
    (net (code "170") (name "unconnected-(IC1-DISP_DATA-PadP$12)") (class "Default")
      (node (ref "IC1") (pin "P$12") (pinfunction "DISP_DATA_P$12") (pintype "bidirectional"))
    )
    (net (code "171") (name "unconnected-(IC1-DISP_DC-PadP$13)") (class "Default")
      (node (ref "IC1") (pin "P$13") (pinfunction "DISP_DC_P$13") (pintype "bidirectional"))
    )
    (net (code "172") (name "unconnected-(IC1-DTR-PadP$3)") (class "Default")
      (node (ref "IC1") (pin "P$3") (pinfunction "DTR_P$3") (pintype "input"))
    )
    (net (code "173") (name "unconnected-(IC1-GPIO1{slash}KBR4-PadP$40)") (class "Default")
      (node (ref "IC1") (pin "P$40") (pinfunction "GPIO1/KBR4_P$40") (pintype "bidirectional"))
    )
    (net (code "174") (name "unconnected-(IC1-GPIO2{slash}KBR3-PadP$41)") (class "Default")
      (node (ref "IC1") (pin "P$41") (pinfunction "GPIO2/KBR3_P$41") (pintype "bidirectional"))
    )
    (net (code "175") (name "unconnected-(IC1-GPIO3{slash}KBR2-PadP$42)") (class "Default")
      (node (ref "IC1") (pin "P$42") (pinfunction "GPIO3/KBR2_P$42") (pintype "bidirectional"))
    )
    (net (code "176") (name "unconnected-(IC1-GPIO4{slash}KBR1-PadP$43)") (class "Default")
      (node (ref "IC1") (pin "P$43") (pinfunction "GPIO4/KBR1_P$43") (pintype "bidirectional"))
    )
    (net (code "177") (name "unconnected-(IC1-GPIO5{slash}KBR0-PadP$44)") (class "Default")
      (node (ref "IC1") (pin "P$44") (pinfunction "GPIO5/KBR0_P$44") (pintype "bidirectional"))
    )
    (net (code "178") (name "unconnected-(IC1-GPIO6{slash}KBC4-PadP$47)") (class "Default")
      (node (ref "IC1") (pin "P$47") (pinfunction "GPIO6/KBC4_P$47") (pintype "bidirectional"))
    )
    (net (code "179") (name "unconnected-(IC1-GPIO7{slash}KBC3-PadP$48)") (class "Default")
      (node (ref "IC1") (pin "P$48") (pinfunction "GPIO7/KBC3_P$48") (pintype "bidirectional"))
    )
    (net (code "180") (name "unconnected-(IC1-GPIO8{slash}KBC2-PadP$49)") (class "Default")
      (node (ref "IC1") (pin "P$49") (pinfunction "GPIO8/KBC2_P$49") (pintype "bidirectional"))
    )
    (net (code "181") (name "unconnected-(IC1-GPIO9{slash}KBC1-PadP$50)") (class "Default")
      (node (ref "IC1") (pin "P$50") (pinfunction "GPIO9/KBC1_P$50") (pintype "bidirectional"))
    )
    (net (code "182") (name "unconnected-(IC1-GPIO10-PadP$51)") (class "Default")
      (node (ref "IC1") (pin "P$51") (pinfunction "GPIO10_P$51") (pintype "bidirectional"))
    )
    (net (code "183") (name "unconnected-(IC1-LINEIN_L-PadP$24)") (class "Default")
      (node (ref "IC1") (pin "P$24") (pinfunction "LINEIN_L_P$24") (pintype "bidirectional"))
    )
    (net (code "184") (name "unconnected-(IC1-LINEIN_R-PadP$23)") (class "Default")
      (node (ref "IC1") (pin "P$23") (pinfunction "LINEIN_R_P$23") (pintype "bidirectional"))
    )
    (net (code "185") (name "unconnected-(IC1-MIC_N-PadP$20)") (class "Default")
      (node (ref "IC1") (pin "P$20") (pinfunction "MIC_N_P$20") (pintype "bidirectional"))
    )
    (net (code "186") (name "unconnected-(IC1-MIC_P-PadP$19)") (class "Default")
      (node (ref "IC1") (pin "P$19") (pinfunction "MIC_P_P$19") (pintype "bidirectional"))
    )
    (net (code "187") (name "unconnected-(IC1-NC-PadP$2)") (class "Default")
      (node (ref "IC1") (pin "P$2") (pinfunction "NC_P$2") (pintype "no_connect"))
    )
    (net (code "188") (name "unconnected-(IC1-NC-PadP$6)") (class "Default")
      (node (ref "IC1") (pin "P$6") (pinfunction "NC_P$6") (pintype "no_connect"))
    )
    (net (code "189") (name "unconnected-(IC1-PWM1-PadP$35)") (class "Default")
      (node (ref "IC1") (pin "P$35") (pinfunction "PWM1_P$35") (pintype "bidirectional"))
    )
    (net (code "190") (name "unconnected-(IC1-PWM2-PadP$36)") (class "Default")
      (node (ref "IC1") (pin "P$36") (pinfunction "PWM2_P$36") (pintype "bidirectional"))
    )
    (net (code "191") (name "unconnected-(IC1-RI-PadP$4)") (class "Default")
      (node (ref "IC1") (pin "P$4") (pinfunction "RI_P$4") (pintype "output"))
    )
    (net (code "192") (name "unconnected-(IC1-RTS-PadP$8)") (class "Default")
      (node (ref "IC1") (pin "P$8") (pinfunction "RTS_P$8") (pintype "input"))
    )
    (net (code "193") (name "unconnected-(IC1-SCL-PadP$38)") (class "Default")
      (node (ref "IC1") (pin "P$38") (pinfunction "SCL_P$38") (pintype "bidirectional"))
    )
    (net (code "194") (name "unconnected-(IC1-SDA-PadP$37)") (class "Default")
      (node (ref "IC1") (pin "P$37") (pinfunction "SDA_P$37") (pintype "bidirectional"))
    )
    (net (code "195") (name "unconnected-(IC1-SIM_PRESENCE-PadP$34)") (class "Default")
      (node (ref "IC1") (pin "P$34") (pinfunction "SIM_PRESENCE_P$34") (pintype "bidirectional"))
    )
    (net (code "196") (name "unconnected-(IC1-SPK_N-PadP$22)") (class "Default")
      (node (ref "IC1") (pin "P$22") (pinfunction "SPK_N_P$22") (pintype "bidirectional"))
    )
    (net (code "197") (name "unconnected-(IC1-SPK_P-PadP$21)") (class "Default")
      (node (ref "IC1") (pin "P$21") (pinfunction "SPK_P_P$21") (pintype "bidirectional"))
    )
    (net (code "198") (name "unconnected-(IC1-VDD_EXT-PadP$15)") (class "Default")
      (node (ref "IC1") (pin "P$15") (pinfunction "VDD_EXT_P$15") (pintype "bidirectional"))
    )
    (net (code "199") (name "unconnected-(IC3A-QH*-Pad9)") (class "Default")
      (node (ref "IC3") (pin "9") (pinfunction "QH*_9") (pintype "tri_state"))
    )
    (net (code "200") (name "unconnected-(SENSOR-DHT-Pad3)") (class "Default")
      (node (ref "SENSOR-DHT") (pin "3") (pinfunction "3_3") (pintype "passive"))
    )
    (net (code "201") (name "unconnected-(SIM_HOLDER-VPP-Pad5)") (class "Default")
      (node (ref "SIM_HOLDER") (pin "5") (pinfunction "VPP_5") (pintype "bidirectional"))
    )
    (net (code "202") (name "unconnected-(STM_CHIP-PA0-WKUP1-Pad14)") (class "Default")
      (node (ref "STM_CHIP") (pin "14") (pinfunction "PA0-WKUP1_14") (pintype "bidirectional"))
    )
    (net (code "203") (name "unconnected-(STM_CHIP-PA8-Pad41)") (class "Default")
      (node (ref "STM_CHIP") (pin "41") (pinfunction "PA8_41") (pintype "bidirectional"))
    )
    (net (code "204") (name "unconnected-(STM_CHIP-PA11-Pad44)") (class "Default")
      (node (ref "STM_CHIP") (pin "44") (pinfunction "PA11_44") (pintype "bidirectional"))
    )
    (net (code "205") (name "unconnected-(STM_CHIP-PA12-Pad45)") (class "Default")
      (node (ref "STM_CHIP") (pin "45") (pinfunction "PA12_45") (pintype "bidirectional"))
    )
    (net (code "206") (name "unconnected-(STM_CHIP-PB3-Pad55)") (class "Default")
      (node (ref "STM_CHIP") (pin "55") (pinfunction "PB3_55") (pintype "bidirectional"))
    )
    (net (code "207") (name "unconnected-(STM_CHIP-PB11-Pad30)") (class "Default")
      (node (ref "STM_CHIP") (pin "30") (pinfunction "PB11_30") (pintype "bidirectional"))
    )
    (net (code "208") (name "unconnected-(STM_CHIP-PC7-Pad38)") (class "Default")
      (node (ref "STM_CHIP") (pin "38") (pinfunction "PC7_38") (pintype "bidirectional"))
    )
    (net (code "209") (name "unconnected-(STM_CHIP-PC8-Pad39)") (class "Default")
      (node (ref "STM_CHIP") (pin "39") (pinfunction "PC8_39") (pintype "bidirectional"))
    )
    (net (code "210") (name "unconnected-(STM_CHIP-PC13-RTC_AF1-WKUP2-Pad2)") (class "Default")
      (node (ref "STM_CHIP") (pin "2") (pinfunction "PC13-RTC_AF1-WKUP2_2") (pintype "bidirectional"))
    )
    (net (code "211") (name "unconnected-(STM_CHIP-PH0_-OSC_IN-Pad5)") (class "Default")
      (node (ref "STM_CHIP") (pin "5") (pinfunction "PH0_-OSC_IN_5") (pintype "bidirectional"))
    )
    (net (code "212") (name "unconnected-(STM_CHIP-PH1-_OSC_OUT-Pad6)") (class "Default")
      (node (ref "STM_CHIP") (pin "6") (pinfunction "PH1-_OSC_OUT_6") (pintype "bidirectional"))
    )
    (net (code "213") (name "unconnected-(U2-DNC-Pad7)") (class "Default")
      (node (ref "U2") (pin "7") (pinfunction "DNC_7") (pintype "passive"))
    )
    (net (code "214") (name "unconnected-(U2-DUPLED-Pad26)") (class "Default")
      (node (ref "U2") (pin "26") (pinfunction "DUPLED_26") (pintype "passive"))
    )
    (net (code "215") (name "unconnected-(U2-INT_N-Pad36)") (class "Default")
      (node (ref "U2") (pin "36") (pinfunction "INT_N_36") (pintype "passive"))
    )
    (net (code "216") (name "unconnected-(U2-NC-Pad12)") (class "Default")
      (node (ref "U2") (pin "12") (pinfunction "NC_12") (pintype "passive"))
    )
    (net (code "217") (name "unconnected-(U2-NC-Pad13)") (class "Default")
      (node (ref "U2") (pin "13") (pinfunction "NC_13") (pintype "passive"))
    )
    (net (code "218") (name "unconnected-(U2-NC-Pad46)") (class "Default")
      (node (ref "U2") (pin "46") (pinfunction "NC_46") (pintype "passive"))
    )
    (net (code "219") (name "unconnected-(U2-NC-Pad47)") (class "Default")
      (node (ref "U2") (pin "47") (pinfunction "NC_47") (pintype "passive"))
    )
    (net (code "220") (name "unconnected-(U2-SPDLED-Pad24)") (class "Default")
      (node (ref "U2") (pin "24") (pinfunction "SPDLED_24") (pintype "passive"))
    )
    (net (code "221") (name "unconnected-(U2-VBG-Pad18)") (class "Default")
      (node (ref "U2") (pin "18") (pinfunction "VBG_18") (pintype "passive"))
    )
  )
)
